# CLP_RV_A_1.net
KiCad netlist of a schematic drawn in Altium Designer
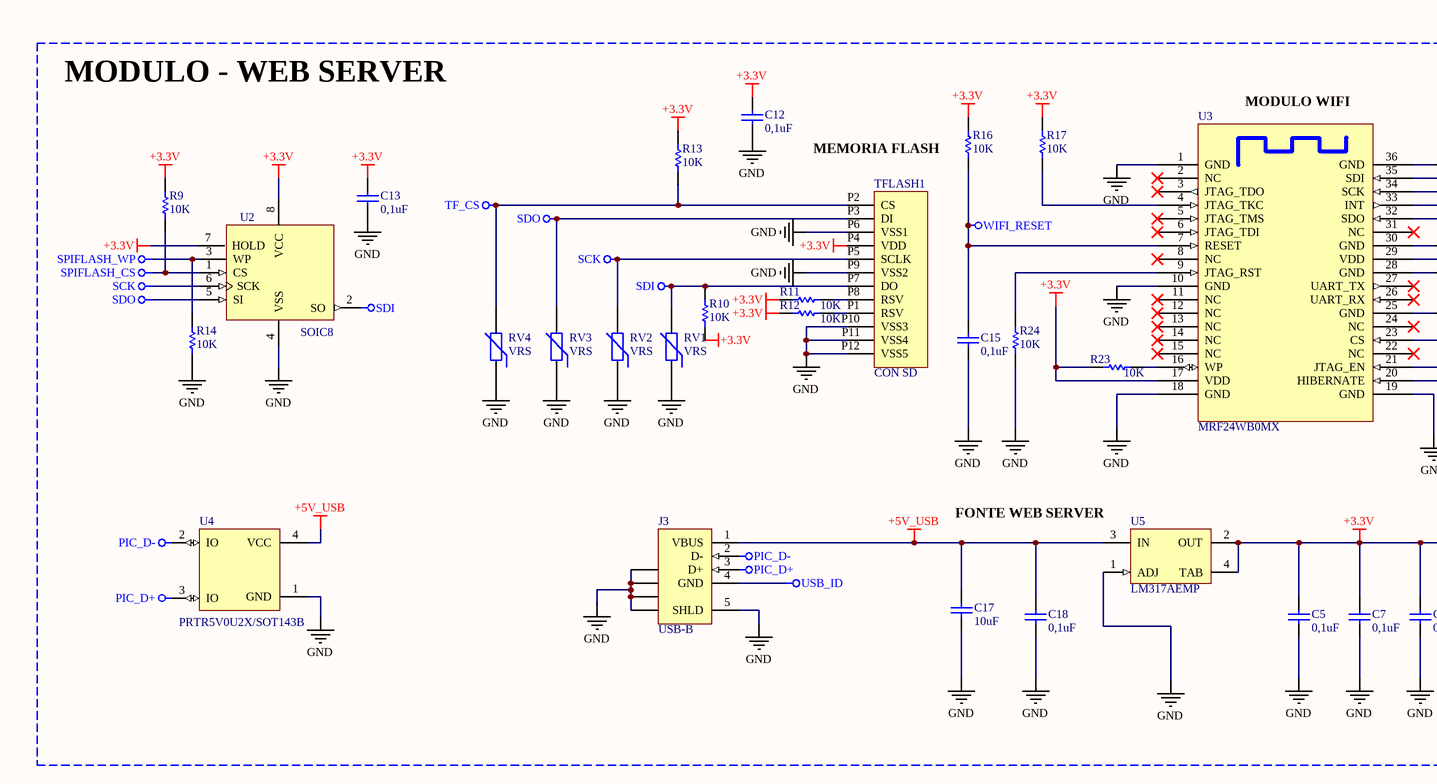
[diagram p0: CLP_RV_A.1.SchDoc, top left]
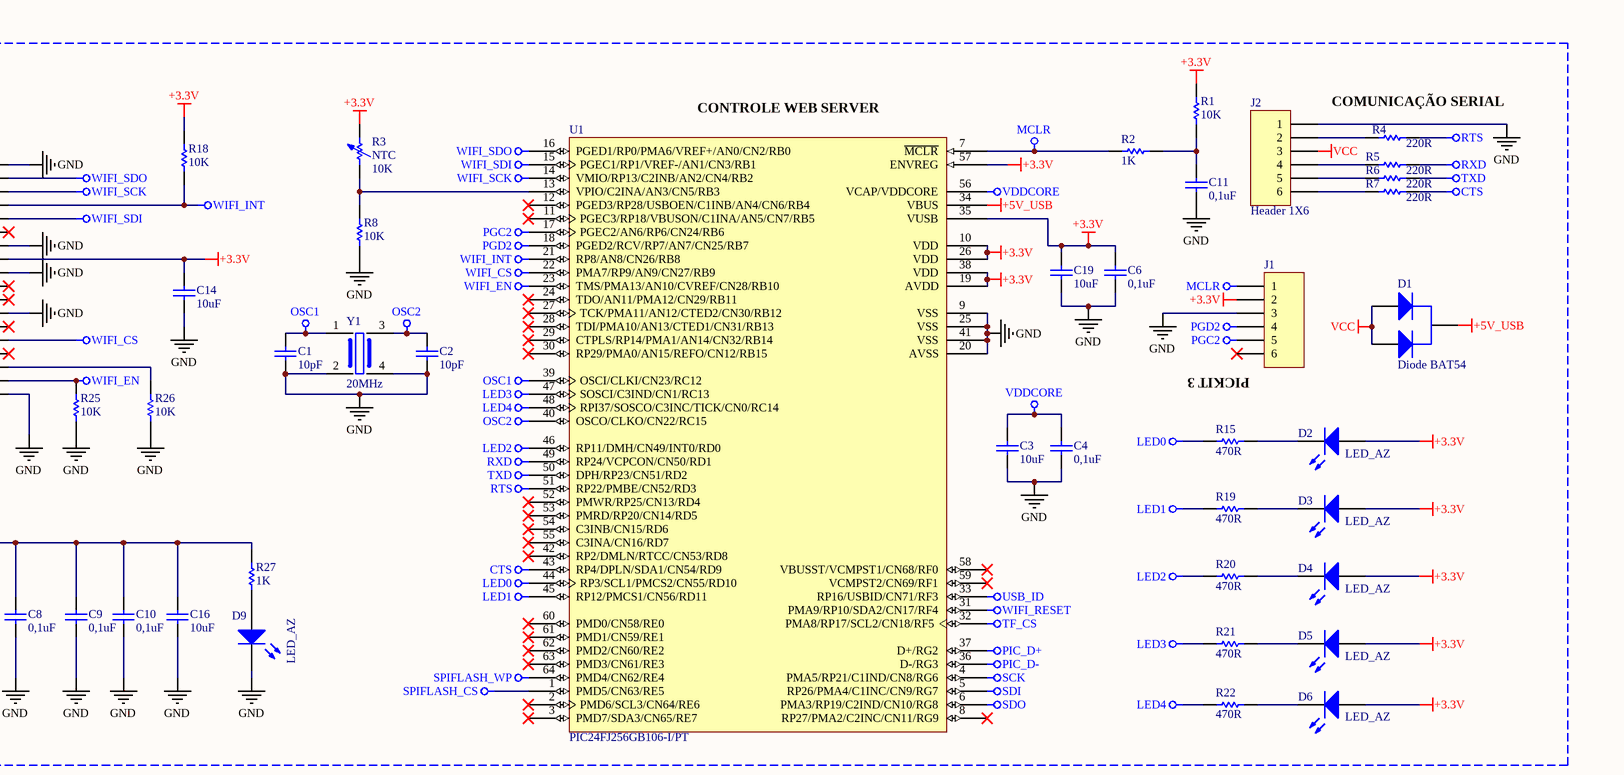
[diagram p1: CLP_RV_A.1.SchDoc, top right]
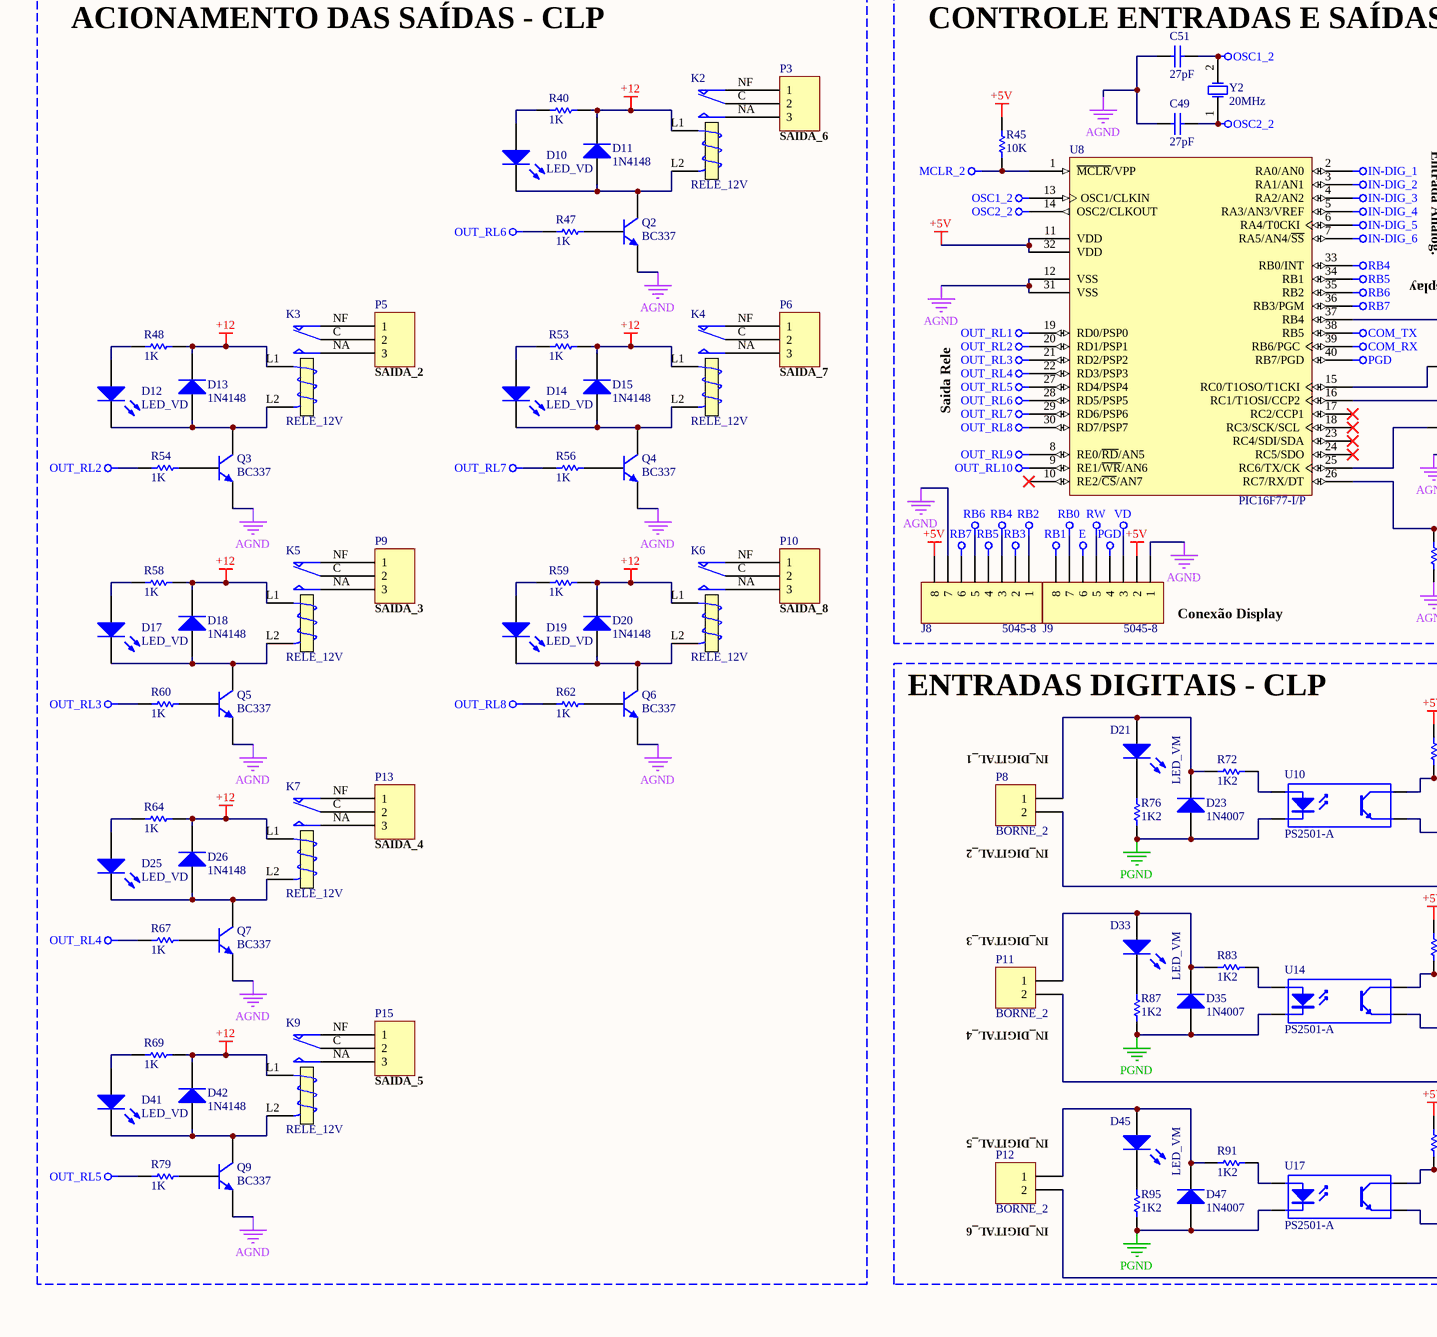
[diagram p2: CLP_RV_A.1.SchDoc, bottom left]
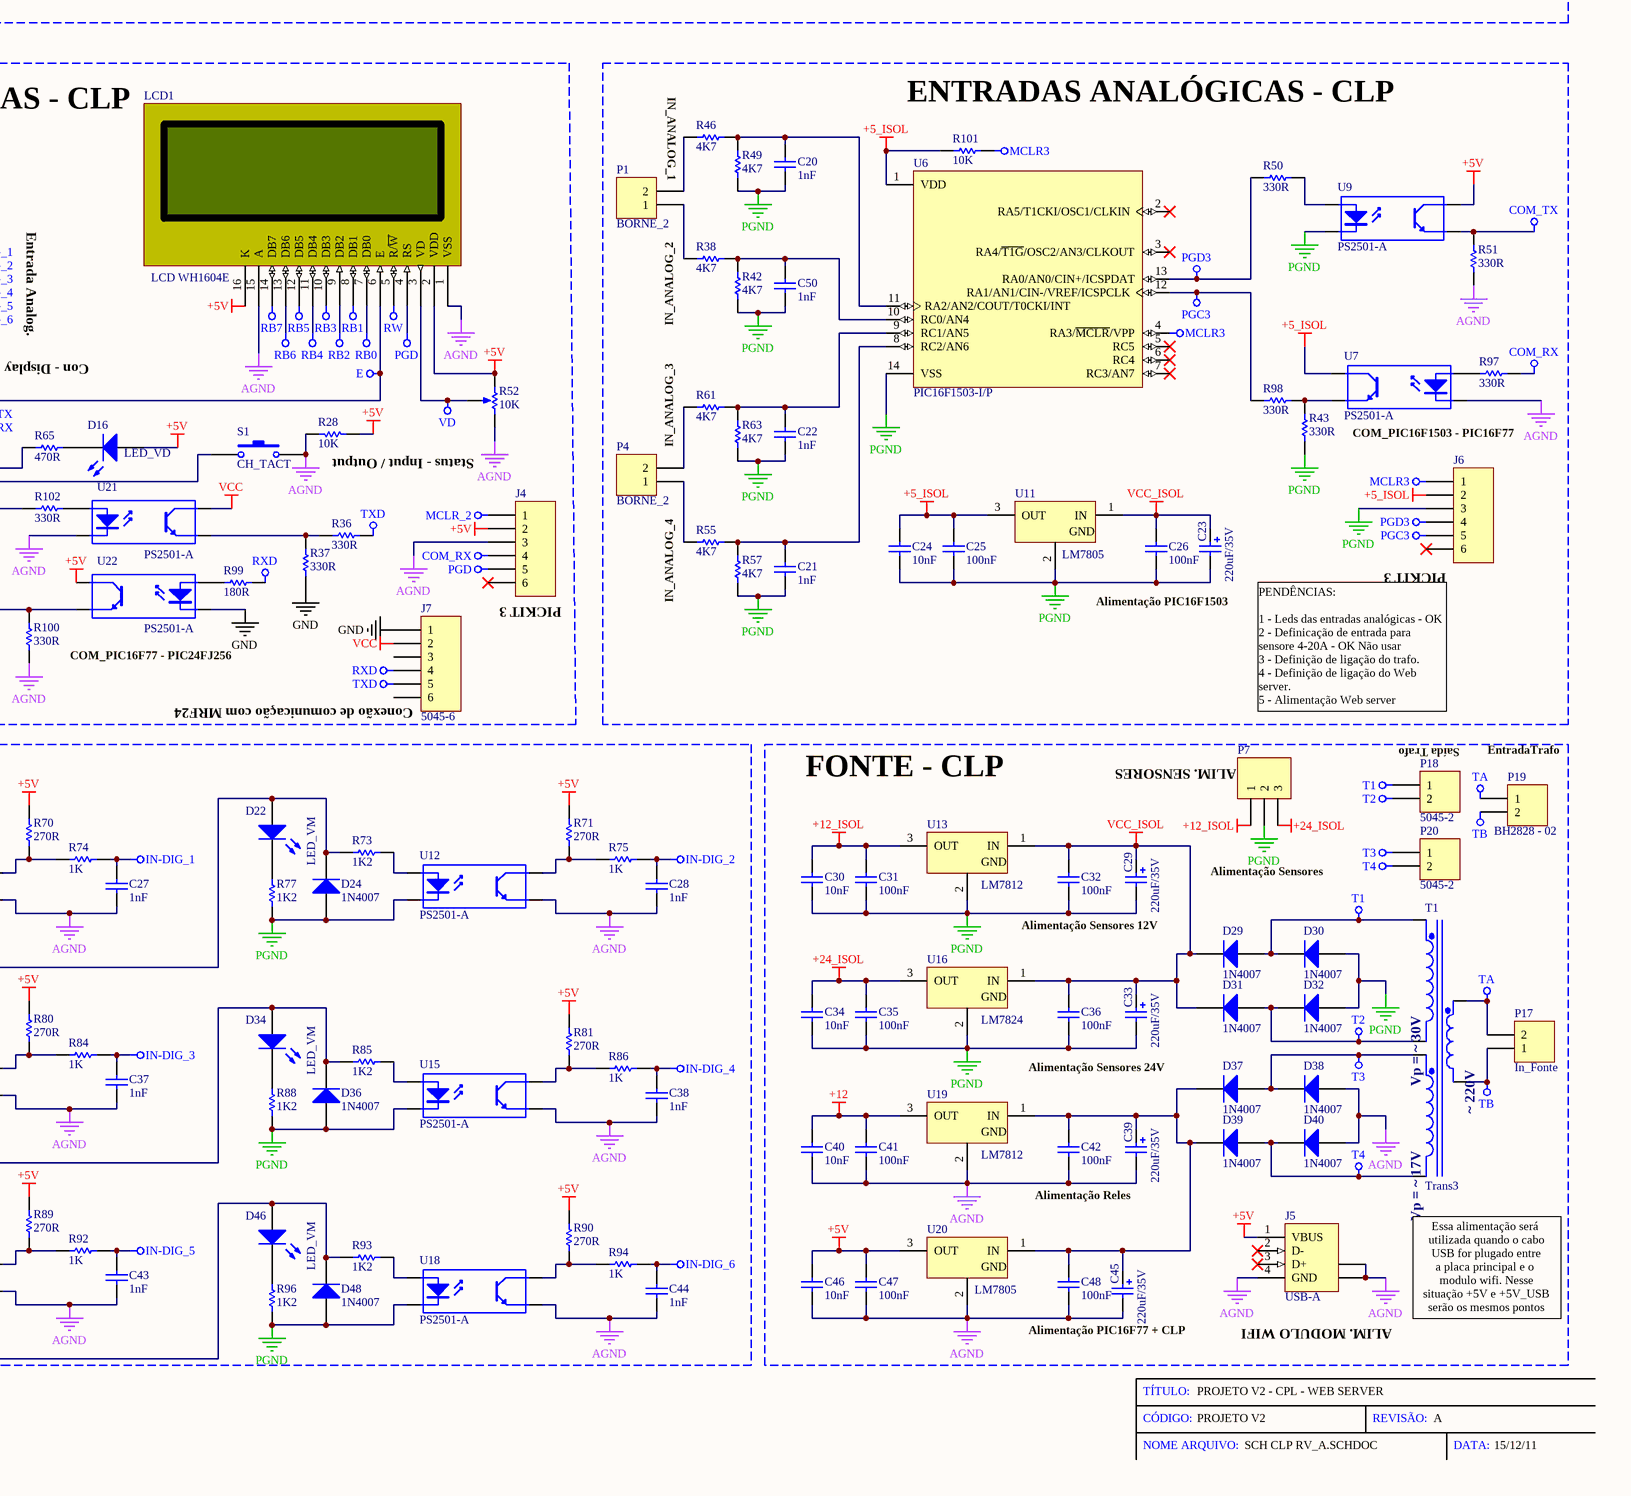
[diagram p3: CLP_RV_A.1.SchDoc, bottom right]

(export (version "E")
  (design (tool "Eeschema 10.0.6"))
  (components
    (comp (ref "C1")
      (value "10pF")
      (footprint "AR_0603_C")
      (description "CAP 0603 10pF - SMD")
      (fields (field (name "PUBLISHER") "Altium Limited"))
      (libsource (lib "LIB") (part "CAP 0603 10pF - SMD"))
    )
    (comp (ref "C2")
      (value "10pF")
      (footprint "AR_0603_C")
      (description "CAP 0603 10pF - SMD")
      (fields (field (name "PUBLISHER") "Altium Limited"))
      (libsource (lib "LIB") (part "CAP 0603 10pF - SMD"))
    )
    (comp (ref "C3")
      (value "10uF")
      (footprint "AR_0805_C")
      (description "CAP 0805 10uF - SMD")
      (fields (field (name "PUBLISHER") "Altium Limited"))
      (libsource (lib "LIB") (part "CAP 0805 10uF - SMD"))
    )
    (comp (ref "C4")
      (value "0,1uF")
      (footprint "AR_0603_C")
      (description "CAP 0603 0,1uF - SMD")
      (fields (field (name "PUBLISHER") "Altium Limited"))
      (libsource (lib "LIB") (part "CAP 0603 0,1uF - SMD"))
    )
    (comp (ref "C5")
      (value "0,1uF")
      (footprint "AR_0603_C")
      (description "CAP 0603 0,1uF - SMD")
      (fields (field (name "PUBLISHER") "Altium Limited"))
      (libsource (lib "LIB") (part "CAP 0603 0,1uF - SMD"))
    )
    (comp (ref "C6")
      (value "0,1uF")
      (footprint "AR_0603_C")
      (description "CAP 0603 0,1uF - SMD")
      (fields (field (name "PUBLISHER") "Altium Limited"))
      (libsource (lib "LIB") (part "CAP 0603 0,1uF - SMD"))
    )
    (comp (ref "C7")
      (value "0,1uF")
      (footprint "AR_0603_C")
      (description "CAP 0603 0,1uF - SMD")
      (fields (field (name "PUBLISHER") "Altium Limited"))
      (libsource (lib "LIB") (part "CAP 0603 0,1uF - SMD"))
    )
    (comp (ref "C8")
      (value "0,1uF")
      (footprint "AR_0603_C")
      (description "CAP 0603 0,1uF - SMD")
      (fields (field (name "PUBLISHER") "Altium Limited"))
      (libsource (lib "LIB") (part "CAP 0603 0,1uF - SMD"))
    )
    (comp (ref "C9")
      (value "0,1uF")
      (footprint "AR_0603_C")
      (description "CAP 0603 0,1uF - SMD")
      (fields (field (name "PUBLISHER") "Altium Limited"))
      (libsource (lib "LIB") (part "CAP 0603 0,1uF - SMD"))
    )
    (comp (ref "C10")
      (value "0,1uF")
      (footprint "AR_0603_C")
      (description "CAP 0603 0,1uF - SMD")
      (fields (field (name "PUBLISHER") "Altium Limited"))
      (libsource (lib "LIB") (part "CAP 0603 0,1uF - SMD"))
    )
    (comp (ref "C11")
      (value "0,1uF")
      (footprint "AR_0603_C")
      (description "CAP 0603 0,1uF - SMD")
      (fields (field (name "PUBLISHER") "Altium Limited"))
      (libsource (lib "LIB") (part "CAP 0603 0,1uF - SMD"))
    )
    (comp (ref "C12")
      (value "0,1uF")
      (footprint "AR_0603_C")
      (description "CAP 0603 0,1uF - SMD")
      (fields (field (name "PUBLISHER") "Altium Limited"))
      (libsource (lib "LIB") (part "CAP 0603 0,1uF - SMD"))
    )
    (comp (ref "C13")
      (value "0,1uF")
      (footprint "AR_0603_C")
      (description "CAP 0603 0,1uF - SMD")
      (fields (field (name "PUBLISHER") "Altium Limited"))
      (libsource (lib "LIB") (part "CAP 0603 0,1uF - SMD"))
    )
    (comp (ref "C14")
      (value "10uF")
      (footprint "AR_0805_C")
      (description "CAP 0805 10uF - SMD")
      (fields (field (name "PUBLISHER") "Altium Limited"))
      (libsource (lib "LIB") (part "CAP 0805 10uF - SMD"))
    )
    (comp (ref "C15")
      (value "0,1uF")
      (footprint "AR_0603_C")
      (description "CAP 0603 0,1uF - SMD")
      (fields (field (name "PUBLISHER") "Altium Limited"))
      (libsource (lib "LIB") (part "CAP 0603 0,1uF - SMD"))
    )
    (comp (ref "C16")
      (value "10uF")
      (footprint "AR_0805_C")
      (description "CAP 0805 10uF - SMD")
      (fields (field (name "PUBLISHER") "Altium Limited"))
      (libsource (lib "LIB") (part "CAP 0805 10uF - SMD"))
    )
    (comp (ref "C17")
      (value "10uF")
      (footprint "AR_0805_C")
      (description "CAP 0805 10uF - SMD")
      (fields (field (name "PUBLISHER") "Altium Limited"))
      (libsource (lib "LIB") (part "CAP 0805 10uF - SMD"))
    )
    (comp (ref "C18")
      (value "0,1uF")
      (footprint "AR_0603_C")
      (description "CAP 0603 0,1uF - SMD")
      (fields (field (name "PUBLISHER") "Altium Limited"))
      (libsource (lib "LIB") (part "CAP 0603 0,1uF - SMD"))
    )
    (comp (ref "C19")
      (value "10uF")
      (footprint "AR_0805_C")
      (description "CAP 0805 10uF - SMD")
      (fields (field (name "PUBLISHER") "Altium Limited"))
      (libsource (lib "LIB") (part "CAP 0805 10uF - SMD"))
    )
    (comp (ref "C20")
      (value "1nF")
      (footprint "CAP_AX_5_CER")
      (description "CAP CER 1nF / 25V")
      (fields (field (name "PUBLISHER") "Altium Limited"))
      (libsource (lib "LIB") (part "CAP CER 1nF / 25V"))
    )
    (comp (ref "C21")
      (value "1nF")
      (footprint "CAP_AX_5_CER")
      (description "CAP CER 1nF / 25V")
      (fields (field (name "PUBLISHER") "Altium Limited"))
      (libsource (lib "LIB") (part "CAP CER 1nF / 25V"))
    )
    (comp (ref "C22")
      (value "1nF")
      (footprint "CAP_AX_5_CER")
      (description "CAP CER 1nF / 25V")
      (fields (field (name "PUBLISHER") "Altium Limited"))
      (libsource (lib "LIB") (part "CAP CER 1nF / 25V"))
    )
    (comp (ref "C23")
      (value "220uF/35V")
      (footprint "CAP_RD_5_10")
      (description "CAP ELCO 220uF / 35V")
      (fields (field (name "PUBLISHER") "Altium Limited"))
      (libsource (lib "LIB") (part "CAP ELCO 220uF / 35V"))
    )
    (comp (ref "C24")
      (value "10nF")
      (footprint "CAP_AX_5_CER")
      (description "CAP CER 10nF / 25V")
      (fields (field (name "PUBLISHER") "Altium Limited"))
      (libsource (lib "LIB") (part "CAP CER 10nF / 25V"))
    )
    (comp (ref "C25")
      (value "100nF")
      (footprint "CAP_AX_5")
      (description "CAP CER 100nF / 63V")
      (fields (field (name "PUBLISHER") "Altium Limited"))
      (libsource (lib "LIB") (part "CAP CER 100nF / 63V"))
    )
    (comp (ref "C26")
      (value "100nF")
      (footprint "CAP_AX_5")
      (description "CAP CER 100nF / 63V")
      (fields (field (name "PUBLISHER") "Altium Limited"))
      (libsource (lib "LIB") (part "CAP CER 100nF / 63V"))
    )
    (comp (ref "C27")
      (value "1nF")
      (footprint "CAP_AX_5_CER")
      (description "CAP CER 1nF / 25V")
      (fields (field (name "PUBLISHER") "Altium Limited"))
      (libsource (lib "LIB") (part "CAP CER 1nF / 25V"))
    )
    (comp (ref "C28")
      (value "1nF")
      (footprint "CAP_AX_5_CER")
      (description "CAP CER 1nF / 25V")
      (fields (field (name "PUBLISHER") "Altium Limited"))
      (libsource (lib "LIB") (part "CAP CER 1nF / 25V"))
    )
    (comp (ref "C29")
      (value "220uF/35V")
      (footprint "CAP_RD_5_10")
      (description "CAP ELCO 220uF / 35V")
      (fields (field (name "PUBLISHER") "Altium Limited"))
      (libsource (lib "LIB") (part "CAP ELCO 220uF / 35V"))
    )
    (comp (ref "C30")
      (value "10nF")
      (footprint "CAP_AX_5_CER")
      (description "CAP CER 10nF / 25V")
      (fields (field (name "PUBLISHER") "Altium Limited"))
      (libsource (lib "LIB") (part "CAP CER 10nF / 25V"))
    )
    (comp (ref "C31")
      (value "100nF")
      (footprint "CAP_AX_5")
      (description "CAP CER 100nF / 63V")
      (fields (field (name "PUBLISHER") "Altium Limited"))
      (libsource (lib "LIB") (part "CAP CER 100nF / 63V"))
    )
    (comp (ref "C32")
      (value "100nF")
      (footprint "CAP_AX_5")
      (description "CAP CER 100nF / 63V")
      (fields (field (name "PUBLISHER") "Altium Limited"))
      (libsource (lib "LIB") (part "CAP CER 100nF / 63V"))
    )
    (comp (ref "C33")
      (value "220uF/35V")
      (footprint "CAP_RD_5_10")
      (description "CAP ELCO 220uF / 35V")
      (fields (field (name "PUBLISHER") "Altium Limited"))
      (libsource (lib "LIB") (part "CAP ELCO 220uF / 35V"))
    )
    (comp (ref "C34")
      (value "10nF")
      (footprint "CAP_AX_5_CER")
      (description "CAP CER 10nF / 25V")
      (fields (field (name "PUBLISHER") "Altium Limited"))
      (libsource (lib "LIB") (part "CAP CER 10nF / 25V"))
    )
    (comp (ref "C35")
      (value "100nF")
      (footprint "CAP_AX_5")
      (description "CAP CER 100nF / 63V")
      (fields (field (name "PUBLISHER") "Altium Limited"))
      (libsource (lib "LIB") (part "CAP CER 100nF / 63V"))
    )
    (comp (ref "C36")
      (value "100nF")
      (footprint "CAP_AX_5")
      (description "CAP CER 100nF / 63V")
      (fields (field (name "PUBLISHER") "Altium Limited"))
      (libsource (lib "LIB") (part "CAP CER 100nF / 63V"))
    )
    (comp (ref "C37")
      (value "1nF")
      (footprint "CAP_AX_5_CER")
      (description "CAP CER 1nF / 25V")
      (fields (field (name "PUBLISHER") "Altium Limited"))
      (libsource (lib "LIB") (part "CAP CER 1nF / 25V"))
    )
    (comp (ref "C38")
      (value "1nF")
      (footprint "CAP_AX_5_CER")
      (description "CAP CER 1nF / 25V")
      (fields (field (name "PUBLISHER") "Altium Limited"))
      (libsource (lib "LIB") (part "CAP CER 1nF / 25V"))
    )
    (comp (ref "C39")
      (value "220uF/35V")
      (footprint "CAP_RD_5_10")
      (description "CAP ELCO 220uF / 35V")
      (fields (field (name "PUBLISHER") "Altium Limited"))
      (libsource (lib "LIB") (part "CAP ELCO 220uF / 35V"))
    )
    (comp (ref "C40")
      (value "10nF")
      (footprint "CAP_AX_5_CER")
      (description "CAP CER 10nF / 25V")
      (fields (field (name "PUBLISHER") "Altium Limited"))
      (libsource (lib "LIB") (part "CAP CER 10nF / 25V"))
    )
    (comp (ref "C41")
      (value "100nF")
      (footprint "CAP_AX_5")
      (description "CAP CER 100nF / 63V")
      (fields (field (name "PUBLISHER") "Altium Limited"))
      (libsource (lib "LIB") (part "CAP CER 100nF / 63V"))
    )
    (comp (ref "C42")
      (value "100nF")
      (footprint "CAP_AX_5")
      (description "CAP CER 100nF / 63V")
      (fields (field (name "PUBLISHER") "Altium Limited"))
      (libsource (lib "LIB") (part "CAP CER 100nF / 63V"))
    )
    (comp (ref "C43")
      (value "1nF")
      (footprint "CAP_AX_5_CER")
      (description "CAP CER 1nF / 25V")
      (fields (field (name "PUBLISHER") "Altium Limited"))
      (libsource (lib "LIB") (part "CAP CER 1nF / 25V"))
    )
    (comp (ref "C44")
      (value "1nF")
      (footprint "CAP_AX_5_CER")
      (description "CAP CER 1nF / 25V")
      (fields (field (name "PUBLISHER") "Altium Limited"))
      (libsource (lib "LIB") (part "CAP CER 1nF / 25V"))
    )
    (comp (ref "C45")
      (value "220uF/35V")
      (footprint "CAP_RD_5_10")
      (description "CAP ELCO 220uF / 35V")
      (fields (field (name "PUBLISHER") "Altium Limited"))
      (libsource (lib "LIB") (part "CAP ELCO 220uF / 35V"))
    )
    (comp (ref "C46")
      (value "10nF")
      (footprint "CAP_AX_5_CER")
      (description "CAP CER 10nF / 25V")
      (fields (field (name "PUBLISHER") "Altium Limited"))
      (libsource (lib "LIB") (part "CAP CER 10nF / 25V"))
    )
    (comp (ref "C47")
      (value "100nF")
      (footprint "CAP_AX_5")
      (description "CAP CER 100nF / 63V")
      (fields (field (name "PUBLISHER") "Altium Limited"))
      (libsource (lib "LIB") (part "CAP CER 100nF / 63V"))
    )
    (comp (ref "C48")
      (value "100nF")
      (footprint "CAP_AX_5")
      (description "CAP CER 100nF / 63V")
      (fields (field (name "PUBLISHER") "Altium Limited"))
      (libsource (lib "LIB") (part "CAP CER 100nF / 63V"))
    )
    (comp (ref "C49")
      (value "27pF")
      (footprint "CAP_AX_5_CER")
      (description "CAP CER 27pF / 25V")
      (fields (field (name "PUBLISHER") "Altium Limited"))
      (libsource (lib "LIB") (part "CAP CER 27pF / 25V"))
    )
    (comp (ref "C50")
      (value "1nF")
      (footprint "CAP_AX_5_CER")
      (description "CAP CER 1nF / 25V")
      (fields (field (name "PUBLISHER") "Altium Limited"))
      (libsource (lib "LIB") (part "CAP CER 1nF / 25V"))
    )
    (comp (ref "C51")
      (value "27pF")
      (footprint "CAP_AX_5_CER")
      (description "CAP CER 27pF / 25V")
      (fields (field (name "PUBLISHER") "Altium Limited"))
      (libsource (lib "LIB") (part "CAP CER 27pF / 25V"))
    )
    (comp (ref "D1")
      (value "Diode BAT54")
      (footprint "AR_SOT23")
      (description "Low-Loss RF Switching Diode")
      (libsource (lib "LIB") (part "Diode BAT54"))
    )
    (comp (ref "D2")
      (value "LED_AZ")
      (footprint "AR_0603_L_AZ")
      (description "LED 0603 AZUL - SMD")
      (fields (field (name "PUBLISHER") "Altium Limited"))
      (libsource (lib "LIB") (part "LED 0603 AZUL - SMD"))
    )
    (comp (ref "D3")
      (value "LED_AZ")
      (footprint "AR_0603_L_AZ")
      (description "LED 0603 AZUL - SMD")
      (fields (field (name "PUBLISHER") "Altium Limited"))
      (libsource (lib "LIB") (part "LED 0603 AZUL - SMD"))
    )
    (comp (ref "D4")
      (value "LED_AZ")
      (footprint "AR_0603_L_AZ")
      (description "LED 0603 AZUL - SMD")
      (fields (field (name "PUBLISHER") "Altium Limited"))
      (libsource (lib "LIB") (part "LED 0603 AZUL - SMD"))
    )
    (comp (ref "D5")
      (value "LED_AZ")
      (footprint "AR_0603_L_AZ")
      (description "LED 0603 AZUL - SMD")
      (fields (field (name "PUBLISHER") "Altium Limited"))
      (libsource (lib "LIB") (part "LED 0603 AZUL - SMD"))
    )
    (comp (ref "D6")
      (value "LED_AZ")
      (footprint "AR_0603_L_AZ")
      (description "LED 0603 AZUL - SMD")
      (fields (field (name "PUBLISHER") "Altium Limited"))
      (libsource (lib "LIB") (part "LED 0603 AZUL - SMD"))
    )
    (comp (ref "D9")
      (value "LED_AZ")
      (footprint "AR_0603_L_AZ")
      (description "LED 0603 AZUL - SMD")
      (fields (field (name "PUBLISHER") "Altium Limited"))
      (libsource (lib "LIB") (part "LED 0603 AZUL - SMD"))
    )
    (comp (ref "D10")
      (value "LED_VD")
      (footprint "LED_VD")
      (description "LED_VD_3MM")
      (fields (field (name "PUBLISHER") "Altium Limited"))
      (libsource (lib "LIB") (part "LED_VD_3MM"))
    )
    (comp (ref "D11")
      (value "1N4148")
      (footprint "1N414X")
      (description "DIODO 1N4148")
      (fields (field (name "PUBLISHER") "Altium Limited"))
      (libsource (lib "LIB") (part "DIODO 1N4148"))
    )
    (comp (ref "D12")
      (value "LED_VD")
      (footprint "LED_VD")
      (description "LED_VD_3MM")
      (fields (field (name "PUBLISHER") "Altium Limited"))
      (libsource (lib "LIB") (part "LED_VD_3MM"))
    )
    (comp (ref "D13")
      (value "1N4148")
      (footprint "1N414X")
      (description "DIODO 1N4148")
      (fields (field (name "PUBLISHER") "Altium Limited"))
      (libsource (lib "LIB") (part "DIODO 1N4148"))
    )
    (comp (ref "D14")
      (value "LED_VD")
      (footprint "LED_VD")
      (description "LED_VD_3MM")
      (fields (field (name "PUBLISHER") "Altium Limited"))
      (libsource (lib "LIB") (part "LED_VD_3MM"))
    )
    (comp (ref "D15")
      (value "1N4148")
      (footprint "1N414X")
      (description "DIODO 1N4148")
      (fields (field (name "PUBLISHER") "Altium Limited"))
      (libsource (lib "LIB") (part "DIODO 1N4148"))
    )
    (comp (ref "D16")
      (value "LED_VD")
      (footprint "LED_VD")
      (description "LED_VD_3MM")
      (fields (field (name "PUBLISHER") "Altium Limited"))
      (libsource (lib "LIB") (part "LED_VD_3MM"))
    )
    (comp (ref "D17")
      (value "LED_VD")
      (footprint "LED_VD")
      (description "LED_VD_3MM")
      (fields (field (name "PUBLISHER") "Altium Limited"))
      (libsource (lib "LIB") (part "LED_VD_3MM"))
    )
    (comp (ref "D18")
      (value "1N4148")
      (footprint "1N414X")
      (description "DIODO 1N4148")
      (fields (field (name "PUBLISHER") "Altium Limited"))
      (libsource (lib "LIB") (part "DIODO 1N4148"))
    )
    (comp (ref "D19")
      (value "LED_VD")
      (footprint "LED_VD")
      (description "LED_VD_3MM")
      (fields (field (name "PUBLISHER") "Altium Limited"))
      (libsource (lib "LIB") (part "LED_VD_3MM"))
    )
    (comp (ref "D20")
      (value "1N4148")
      (footprint "1N414X")
      (description "DIODO 1N4148")
      (fields (field (name "PUBLISHER") "Altium Limited"))
      (libsource (lib "LIB") (part "DIODO 1N4148"))
    )
    (comp (ref "D21")
      (value "LED_VM")
      (footprint "LED_VM")
      (description "LED_VM_3MM")
      (fields (field (name "PUBLISHER") "Altium Limited"))
      (libsource (lib "LIB") (part "LED_VM_3MM"))
    )
    (comp (ref "D22")
      (value "LED_VM")
      (footprint "LED_VM")
      (description "LED_VM_3MM")
      (fields (field (name "PUBLISHER") "Altium Limited"))
      (libsource (lib "LIB") (part "LED_VM_3MM"))
    )
    (comp (ref "D23")
      (value "1N4007")
      (footprint "1N400X")
      (description "DIODO 1N4007")
      (fields (field (name "PUBLISHER") "Altium Limited"))
      (libsource (lib "LIB") (part "DIODO 1N4007"))
    )
    (comp (ref "D24")
      (value "1N4007")
      (footprint "1N400X")
      (description "DIODO 1N4007")
      (fields (field (name "PUBLISHER") "Altium Limited"))
      (libsource (lib "LIB") (part "DIODO 1N4007"))
    )
    (comp (ref "D25")
      (value "LED_VD")
      (footprint "LED_VD")
      (description "LED_VD_3MM")
      (fields (field (name "PUBLISHER") "Altium Limited"))
      (libsource (lib "LIB") (part "LED_VD_3MM"))
    )
    (comp (ref "D26")
      (value "1N4148")
      (footprint "1N414X")
      (description "DIODO 1N4148")
      (fields (field (name "PUBLISHER") "Altium Limited"))
      (libsource (lib "LIB") (part "DIODO 1N4148"))
    )
    (comp (ref "D29")
      (value "1N4007")
      (footprint "1N400X")
      (description "DIODO 1N4007")
      (fields (field (name "PUBLISHER") "Altium Limited"))
      (libsource (lib "LIB") (part "DIODO 1N4007"))
    )
    (comp (ref "D30")
      (value "1N4007")
      (footprint "1N400X")
      (description "DIODO 1N4007")
      (fields (field (name "PUBLISHER") "Altium Limited"))
      (libsource (lib "LIB") (part "DIODO 1N4007"))
    )
    (comp (ref "D31")
      (value "1N4007")
      (footprint "1N400X")
      (description "DIODO 1N4007")
      (fields (field (name "PUBLISHER") "Altium Limited"))
      (libsource (lib "LIB") (part "DIODO 1N4007"))
    )
    (comp (ref "D32")
      (value "1N4007")
      (footprint "1N400X")
      (description "DIODO 1N4007")
      (fields (field (name "PUBLISHER") "Altium Limited"))
      (libsource (lib "LIB") (part "DIODO 1N4007"))
    )
    (comp (ref "D33")
      (value "LED_VM")
      (footprint "LED_VM")
      (description "LED_VM_3MM")
      (fields (field (name "PUBLISHER") "Altium Limited"))
      (libsource (lib "LIB") (part "LED_VM_3MM"))
    )
    (comp (ref "D34")
      (value "LED_VM")
      (footprint "LED_VM")
      (description "LED_VM_3MM")
      (fields (field (name "PUBLISHER") "Altium Limited"))
      (libsource (lib "LIB") (part "LED_VM_3MM"))
    )
    (comp (ref "D35")
      (value "1N4007")
      (footprint "1N400X")
      (description "DIODO 1N4007")
      (fields (field (name "PUBLISHER") "Altium Limited"))
      (libsource (lib "LIB") (part "DIODO 1N4007"))
    )
    (comp (ref "D36")
      (value "1N4007")
      (footprint "1N400X")
      (description "DIODO 1N4007")
      (fields (field (name "PUBLISHER") "Altium Limited"))
      (libsource (lib "LIB") (part "DIODO 1N4007"))
    )
    (comp (ref "D37")
      (value "1N4007")
      (footprint "1N400X")
      (description "DIODO 1N4007")
      (fields (field (name "PUBLISHER") "Altium Limited"))
      (libsource (lib "LIB") (part "DIODO 1N4007"))
    )
    (comp (ref "D38")
      (value "1N4007")
      (footprint "1N400X")
      (description "DIODO 1N4007")
      (fields (field (name "PUBLISHER") "Altium Limited"))
      (libsource (lib "LIB") (part "DIODO 1N4007"))
    )
    (comp (ref "D39")
      (value "1N4007")
      (footprint "1N400X")
      (description "DIODO 1N4007")
      (fields (field (name "PUBLISHER") "Altium Limited"))
      (libsource (lib "LIB") (part "DIODO 1N4007"))
    )
    (comp (ref "D40")
      (value "1N4007")
      (footprint "1N400X")
      (description "DIODO 1N4007")
      (fields (field (name "PUBLISHER") "Altium Limited"))
      (libsource (lib "LIB") (part "DIODO 1N4007"))
    )
    (comp (ref "D41")
      (value "LED_VD")
      (footprint "LED_VD")
      (description "LED_VD_3MM")
      (fields (field (name "PUBLISHER") "Altium Limited"))
      (libsource (lib "LIB") (part "LED_VD_3MM"))
    )
    (comp (ref "D42")
      (value "1N4148")
      (footprint "1N414X")
      (description "DIODO 1N4148")
      (fields (field (name "PUBLISHER") "Altium Limited"))
      (libsource (lib "LIB") (part "DIODO 1N4148"))
    )
    (comp (ref "D45")
      (value "LED_VM")
      (footprint "LED_VM")
      (description "LED_VM_3MM")
      (fields (field (name "PUBLISHER") "Altium Limited"))
      (libsource (lib "LIB") (part "LED_VM_3MM"))
    )
    (comp (ref "D46")
      (value "LED_VM")
      (footprint "LED_VM")
      (description "LED_VM_3MM")
      (fields (field (name "PUBLISHER") "Altium Limited"))
      (libsource (lib "LIB") (part "LED_VM_3MM"))
    )
    (comp (ref "D47")
      (value "1N4007")
      (footprint "1N400X")
      (description "DIODO 1N4007")
      (fields (field (name "PUBLISHER") "Altium Limited"))
      (libsource (lib "LIB") (part "DIODO 1N4007"))
    )
    (comp (ref "D48")
      (value "1N4007")
      (footprint "1N400X")
      (description "DIODO 1N4007")
      (fields (field (name "PUBLISHER") "Altium Limited"))
      (libsource (lib "LIB") (part "DIODO 1N4007"))
    )
    (comp (ref "J1")
      (value "Header 1X6")
      (footprint "BARRA DE PINO RETA 1 X 7")
      (description "Barra de Pino 1X6")
      (fields (field (name "PUBLISHER") "Altium Limited"))
      (libsource (lib "") (part "Barra de Pino 1X6_1"))
    )
    (comp (ref "J2")
      (value "Header 1X6")
      (footprint "BARRA DE PINO RETA 1 X 7")
      (description "Barra de Pino 1X6")
      (fields (field (name "PUBLISHER") "Altium Limited"))
      (libsource (lib "LIB") (part "Barra de Pino 1X6"))
    )
    (comp (ref "J3")
      (value "USB-B")
      (footprint "CON_USB_SMD_B")
      (description "USB 2.0, Right Angle, SMT, B Type, Receptacle, 5 Position, Black")
      (fields (field (name "PUBLISHER") "Altium Limited"))
      (libsource (lib "LIB") (part "CON_USB_SMD_B"))
    )
    (comp (ref "J4")
      (value "PICKIT 3")
      (footprint "BARRA DE PINO RETA 1 X 7")
      (description "Barra de Pino 1X6")
      (fields (field (name "PUBLISHER") "Altium Limited"))
      (libsource (lib "") (part "Barra de Pino 1X6_1"))
    )
    (comp (ref "J5")
      (value "USB-A")
      (footprint "CON_USB_PTH_A")
      (description "USB 1.1, Right Angle, Thru-Hole, Reverse Type, Receptacle, 4 Position, Black")
      (fields (field (name "PUBLISHER") "Altium Limited"))
      (libsource (lib "LIB") (part "CON_USB_PTH_A"))
    )
    (comp (ref "J6")
      (value "PICKIT 3")
      (footprint "BARRA DE PINO RETA 1 X 7")
      (description "Barra de Pino 1X6")
      (fields (field (name "PUBLISHER") "Altium Limited"))
      (libsource (lib "") (part "Barra de Pino 1X6_1"))
    )
    (comp (ref "J7")
      (value "5045-6")
      (footprint "BC5045-06")
      (description "BASE CONEC. 5045-6")
      (fields (field (name "PUBLISHER") "Altium Limited"))
      (libsource (lib "LIB") (part "BASE CONEC. 5045-6"))
    )
    (comp (ref "J8")
      (value "5045-8")
      (footprint "BC5045-08")
      (description "BASE CONEC. 5045-8")
      (fields (field (name "PUBLISHER") "Altium Limited"))
      (libsource (lib "LIB") (part "BASE CONEC. 5045-8"))
    )
    (comp (ref "J9")
      (value "5045-8")
      (footprint "BC5045-08")
      (description "BASE CONEC. 5045-8")
      (fields (field (name "PUBLISHER") "Altium Limited"))
      (libsource (lib "LIB") (part "BASE CONEC. 5045-8"))
    )
    (comp (ref "K2")
      (value "RELE_12V")
      (footprint "RELE_M")
      (description "RELE 12V")
      (fields (field (name "PUBLISHER") "Altium Limited"))
      (libsource (lib "LIB") (part "RELE 12V"))
    )
    (comp (ref "K3")
      (value "RELE_12V")
      (footprint "RELE_M")
      (description "RELE 12V")
      (fields (field (name "PUBLISHER") "Altium Limited"))
      (libsource (lib "LIB") (part "RELE 12V"))
    )
    (comp (ref "K4")
      (value "RELE_12V")
      (footprint "RELE_M")
      (description "RELE 12V")
      (fields (field (name "PUBLISHER") "Altium Limited"))
      (libsource (lib "LIB") (part "RELE 12V"))
    )
    (comp (ref "K5")
      (value "RELE_12V")
      (footprint "RELE_M")
      (description "RELE 12V")
      (fields (field (name "PUBLISHER") "Altium Limited"))
      (libsource (lib "LIB") (part "RELE 12V"))
    )
    (comp (ref "K6")
      (value "RELE_12V")
      (footprint "RELE_M")
      (description "RELE 12V")
      (fields (field (name "PUBLISHER") "Altium Limited"))
      (libsource (lib "LIB") (part "RELE 12V"))
    )
    (comp (ref "K7")
      (value "RELE_12V")
      (footprint "RELE_M")
      (description "RELE 12V")
      (fields (field (name "PUBLISHER") "Altium Limited"))
      (libsource (lib "LIB") (part "RELE 12V"))
    )
    (comp (ref "K9")
      (value "RELE_12V")
      (footprint "RELE_M")
      (description "RELE 12V")
      (fields (field (name "PUBLISHER") "Altium Limited"))
      (libsource (lib "LIB") (part "RELE 12V"))
    )
    (comp (ref "LCD1")
      (value "LCD WH1604E")
      (footprint "WH1604")
      (description "Display Crístal Líquido WH1604E - 16X4")
      (libsource (lib "LIB") (part "LCD WH1604E"))
    )
    (comp (ref "P1")
      (value "BORNE_2")
      (footprint "BORNE_2")
      (description "BORNE_MOLEX_2")
      (fields (field (name "PUBLISHER") "Altium Limited"))
      (libsource (lib "") (part "BORNE_MOLEX_2_2"))
    )
    (comp (ref "P3")
      (value "SAIDA_6")
      (footprint "BORNE_3")
      (description "BORNE_MOLEX_3")
      (fields (field (name "PUBLISHER") "Altium Limited"))
      (libsource (lib "LIB") (part "BORNE_MOLEX_3"))
    )
    (comp (ref "P4")
      (value "BORNE_2")
      (footprint "BORNE_2")
      (description "BORNE_MOLEX_2")
      (fields (field (name "PUBLISHER") "Altium Limited"))
      (libsource (lib "") (part "BORNE_MOLEX_2_2"))
    )
    (comp (ref "P5")
      (value "SAIDA_2")
      (footprint "BORNE_3")
      (description "BORNE_MOLEX_3")
      (fields (field (name "PUBLISHER") "Altium Limited"))
      (libsource (lib "LIB") (part "BORNE_MOLEX_3"))
    )
    (comp (ref "P6")
      (value "SAIDA_7")
      (footprint "BORNE_3")
      (description "BORNE_MOLEX_3")
      (fields (field (name "PUBLISHER") "Altium Limited"))
      (libsource (lib "LIB") (part "BORNE_MOLEX_3"))
    )
    (comp (ref "P7")
      (value "Alimentação Sensores")
      (footprint "BORNE_3")
      (description "BORNE_MOLEX_3")
      (fields (field (name "PUBLISHER") "Altium Limited"))
      (libsource (lib "") (part "BORNE_MOLEX_3_1"))
    )
    (comp (ref "P8")
      (value "BORNE_2")
      (footprint "BORNE_2")
      (description "BORNE_MOLEX_2")
      (fields (field (name "PUBLISHER") "Altium Limited"))
      (libsource (lib "LIB") (part "BORNE_MOLEX_2"))
    )
    (comp (ref "P9")
      (value "SAIDA_3")
      (footprint "BORNE_3")
      (description "BORNE_MOLEX_3")
      (fields (field (name "PUBLISHER") "Altium Limited"))
      (libsource (lib "LIB") (part "BORNE_MOLEX_3"))
    )
    (comp (ref "P10")
      (value "SAIDA_8")
      (footprint "BORNE_3")
      (description "BORNE_MOLEX_3")
      (fields (field (name "PUBLISHER") "Altium Limited"))
      (libsource (lib "LIB") (part "BORNE_MOLEX_3"))
    )
    (comp (ref "P11")
      (value "BORNE_2")
      (footprint "BORNE_2")
      (description "BORNE_MOLEX_2")
      (fields (field (name "PUBLISHER") "Altium Limited"))
      (libsource (lib "LIB") (part "BORNE_MOLEX_2"))
    )
    (comp (ref "P12")
      (value "BORNE_2")
      (footprint "BORNE_2")
      (description "BORNE_MOLEX_2")
      (fields (field (name "PUBLISHER") "Altium Limited"))
      (libsource (lib "LIB") (part "BORNE_MOLEX_2"))
    )
    (comp (ref "P13")
      (value "SAIDA_4")
      (footprint "BORNE_3")
      (description "BORNE_MOLEX_3")
      (fields (field (name "PUBLISHER") "Altium Limited"))
      (libsource (lib "LIB") (part "BORNE_MOLEX_3"))
    )
    (comp (ref "P15")
      (value "SAIDA_5")
      (footprint "BORNE_3")
      (description "BORNE_MOLEX_3")
      (fields (field (name "PUBLISHER") "Altium Limited"))
      (libsource (lib "LIB") (part "BORNE_MOLEX_3"))
    )
    (comp (ref "P17")
      (value "In_Fonte")
      (footprint "BORNE_2")
      (description "BORNE_MOLEX_2")
      (fields (field (name "PUBLISHER") "Altium Limited"))
      (libsource (lib "") (part "BORNE_MOLEX_2_1"))
    )
    (comp (ref "P18")
      (value "5045-2")
      (footprint "BC5045-02")
      (description "BASE CONEC. 5045-2")
      (fields (field (name "PUBLISHER") "Altium Limited"))
      (libsource (lib "LIB") (part "BASE CONEC. 5045-2"))
    )
    (comp (ref "P19")
      (value "BH2828 - 02")
      (footprint "BOX_HEAD_2828-02")
      (description "Box Header BH2828 - 02")
      (fields (field (name "PUBLISHER") "Altium Limited"))
      (libsource (lib "LIB") (part "Box Header BH2828 - 02"))
    )
    (comp (ref "P20")
      (value "5045-2")
      (footprint "BC5045-02")
      (description "BASE CONEC. 5045-2")
      (fields (field (name "PUBLISHER") "Altium Limited"))
      (libsource (lib "LIB") (part "BASE CONEC. 5045-2"))
    )
    (comp (ref "Q2")
      (value "BC337")
      (footprint "TO-92")
      (description "TR BC337")
      (fields (field (name "PUBLISHER") "Altium Limited"))
      (libsource (lib "LIB") (part "TR BC337"))
    )
    (comp (ref "Q3")
      (value "BC337")
      (footprint "TO-92")
      (description "TR BC337")
      (fields (field (name "PUBLISHER") "Altium Limited"))
      (libsource (lib "LIB") (part "TR BC337"))
    )
    (comp (ref "Q4")
      (value "BC337")
      (footprint "TO-92")
      (description "TR BC337")
      (fields (field (name "PUBLISHER") "Altium Limited"))
      (libsource (lib "LIB") (part "TR BC337"))
    )
    (comp (ref "Q5")
      (value "BC337")
      (footprint "TO-92")
      (description "TR BC337")
      (fields (field (name "PUBLISHER") "Altium Limited"))
      (libsource (lib "LIB") (part "TR BC337"))
    )
    (comp (ref "Q6")
      (value "BC337")
      (footprint "TO-92")
      (description "TR BC337")
      (fields (field (name "PUBLISHER") "Altium Limited"))
      (libsource (lib "LIB") (part "TR BC337"))
    )
    (comp (ref "Q7")
      (value "BC337")
      (footprint "TO-92")
      (description "TR BC337")
      (fields (field (name "PUBLISHER") "Altium Limited"))
      (libsource (lib "LIB") (part "TR BC337"))
    )
    (comp (ref "Q9")
      (value "BC337")
      (footprint "TO-92")
      (description "TR BC337")
      (fields (field (name "PUBLISHER") "Altium Limited"))
      (libsource (lib "LIB") (part "TR BC337"))
    )
    (comp (ref "R1")
      (value "10K")
      (footprint "AR_0603_R")
      (description "RES 10K 0603 - SMD")
      (fields (field (name "PUBLISHER") "Altium Limited"))
      (libsource (lib "LIB") (part "RES 10K 0603 - SMD"))
    )
    (comp (ref "R2")
      (value "1K")
      (footprint "AR_0603_R")
      (description "RES 1K 0603 - SMD")
      (fields (field (name "PUBLISHER") "Altium Limited"))
      (libsource (lib "LIB") (part "RES 1K 0603 - SMD"))
    )
    (comp (ref "R3")
      (value "NTC")
      (footprint "AR_0603_I")
      (description "Variable Resistor")
      (fields (field (name "ALTIUM_VALUE") "10K") (field (name "PUBLISHER") "Altium Limited"))
      (libsource (lib "Miscellaneous Devices") (part "Res Adj1"))
    )
    (comp (ref "R4")
      (value "220R")
      (footprint "AR_0603_R")
      (description "RES 220R 0603 - SMD")
      (fields (field (name "PUBLISHER") "Altium Limited"))
      (libsource (lib "LIB") (part "RES 220R 0603 - SMD"))
    )
    (comp (ref "R5")
      (value "220R")
      (footprint "AR_0603_R")
      (description "RES 220R 0603 - SMD")
      (fields (field (name "PUBLISHER") "Altium Limited"))
      (libsource (lib "LIB") (part "RES 220R 0603 - SMD"))
    )
    (comp (ref "R6")
      (value "220R")
      (footprint "AR_0603_R")
      (description "RES 220R 0603 - SMD")
      (fields (field (name "PUBLISHER") "Altium Limited"))
      (libsource (lib "LIB") (part "RES 220R 0603 - SMD"))
    )
    (comp (ref "R7")
      (value "220R")
      (footprint "AR_0603_R")
      (description "RES 220R 0603 - SMD")
      (fields (field (name "PUBLISHER") "Altium Limited"))
      (libsource (lib "LIB") (part "RES 220R 0603 - SMD"))
    )
    (comp (ref "R8")
      (value "10K")
      (footprint "AR_0603_R")
      (description "RES 10K 0603 - SMD")
      (fields (field (name "PUBLISHER") "Altium Limited"))
      (libsource (lib "LIB") (part "RES 10K 0603 - SMD"))
    )
    (comp (ref "R9")
      (value "10K")
      (footprint "AR_0603_R")
      (description "RES 10K 0603 - SMD")
      (fields (field (name "PUBLISHER") "Altium Limited"))
      (libsource (lib "LIB") (part "RES 10K 0603 - SMD"))
    )
    (comp (ref "R10")
      (value "10K")
      (footprint "AR_0603_R")
      (description "RES 10K 0603 - SMD")
      (fields (field (name "PUBLISHER") "Altium Limited"))
      (libsource (lib "LIB") (part "RES 10K 0603 - SMD"))
    )
    (comp (ref "R11")
      (value "10K")
      (footprint "AR_0603_R")
      (description "RES 10K 0603 - SMD")
      (fields (field (name "PUBLISHER") "Altium Limited"))
      (libsource (lib "LIB") (part "RES 10K 0603 - SMD"))
    )
    (comp (ref "R12")
      (value "10K")
      (footprint "AR_0603_R")
      (description "RES 10K 0603 - SMD")
      (fields (field (name "PUBLISHER") "Altium Limited"))
      (libsource (lib "LIB") (part "RES 10K 0603 - SMD"))
    )
    (comp (ref "R13")
      (value "10K")
      (footprint "AR_0603_R")
      (description "RES 10K 0603 - SMD")
      (fields (field (name "PUBLISHER") "Altium Limited"))
      (libsource (lib "LIB") (part "RES 10K 0603 - SMD"))
    )
    (comp (ref "R14")
      (value "10K")
      (footprint "AR_0603_R")
      (description "RES 10K 0603 - SMD")
      (fields (field (name "PUBLISHER") "Altium Limited"))
      (libsource (lib "LIB") (part "RES 10K 0603 - SMD"))
    )
    (comp (ref "R15")
      (value "470R")
      (footprint "AR_0603_R")
      (description "RES 470R 0603 - SMD")
      (fields (field (name "PUBLISHER") "Altium Limited"))
      (libsource (lib "LIB") (part "RES 470R 0603 - SMD"))
    )
    (comp (ref "R16")
      (value "10K")
      (footprint "AR_0603_R")
      (description "RES 10K 0603 - SMD")
      (fields (field (name "PUBLISHER") "Altium Limited"))
      (libsource (lib "LIB") (part "RES 10K 0603 - SMD"))
    )
    (comp (ref "R17")
      (value "10K")
      (footprint "AR_0603_R")
      (description "RES 10K 0603 - SMD")
      (fields (field (name "PUBLISHER") "Altium Limited"))
      (libsource (lib "LIB") (part "RES 10K 0603 - SMD"))
    )
    (comp (ref "R18")
      (value "10K")
      (footprint "AR_0603_R")
      (description "RES 10K 0603 - SMD")
      (fields (field (name "PUBLISHER") "Altium Limited"))
      (libsource (lib "LIB") (part "RES 10K 0603 - SMD"))
    )
    (comp (ref "R19")
      (value "470R")
      (footprint "AR_0603_R")
      (description "RES 470R 0603 - SMD")
      (fields (field (name "PUBLISHER") "Altium Limited"))
      (libsource (lib "LIB") (part "RES 470R 0603 - SMD"))
    )
    (comp (ref "R20")
      (value "470R")
      (footprint "AR_0603_R")
      (description "RES 470R 0603 - SMD")
      (fields (field (name "PUBLISHER") "Altium Limited"))
      (libsource (lib "LIB") (part "RES 470R 0603 - SMD"))
    )
    (comp (ref "R21")
      (value "470R")
      (footprint "AR_0603_R")
      (description "RES 470R 0603 - SMD")
      (fields (field (name "PUBLISHER") "Altium Limited"))
      (libsource (lib "LIB") (part "RES 470R 0603 - SMD"))
    )
    (comp (ref "R22")
      (value "470R")
      (footprint "AR_0603_R")
      (description "RES 470R 0603 - SMD")
      (fields (field (name "PUBLISHER") "Altium Limited"))
      (libsource (lib "LIB") (part "RES 470R 0603 - SMD"))
    )
    (comp (ref "R23")
      (value "10K")
      (footprint "AR_0603_R")
      (description "RES 10K 0603 - SMD")
      (fields (field (name "PUBLISHER") "Altium Limited"))
      (libsource (lib "LIB") (part "RES 10K 0603 - SMD"))
    )
    (comp (ref "R24")
      (value "10K")
      (footprint "AR_0603_R")
      (description "RES 10K 0603 - SMD")
      (fields (field (name "PUBLISHER") "Altium Limited"))
      (libsource (lib "LIB") (part "RES 10K 0603 - SMD"))
    )
    (comp (ref "R25")
      (value "10K")
      (footprint "AR_0603_R")
      (description "RES 10K 0603 - SMD")
      (fields (field (name "PUBLISHER") "Altium Limited"))
      (libsource (lib "LIB") (part "RES 10K 0603 - SMD"))
    )
    (comp (ref "R26")
      (value "10K")
      (footprint "AR_0603_R")
      (description "RES 10K 0603 - SMD")
      (fields (field (name "PUBLISHER") "Altium Limited"))
      (libsource (lib "LIB") (part "RES 10K 0603 - SMD"))
    )
    (comp (ref "R27")
      (value "1K")
      (footprint "AR_0603_R")
      (description "RES 1K 0603 - SMD")
      (fields (field (name "PUBLISHER") "Altium Limited"))
      (libsource (lib "LIB") (part "RES 1K 0603 - SMD"))
    )
    (comp (ref "R28")
      (value "10K")
      (footprint "R20")
      (description "RES 10K 1/8W - PTH")
      (fields (field (name "PUBLISHER") "Altium Limited"))
      (libsource (lib "") (part "RES 10K 1/8W - PTH_1"))
    )
    (comp (ref "R36")
      (value "330R")
      (footprint "R20")
      (description "RES 330R 1/8W - PTH")
      (fields (field (name "Comment") "4K7") (field (name "PUBLISHER") "Altium Limited"))
      (libsource (lib "LIB") (part "RES 330R 1/8W - PTH"))
    )
    (comp (ref "R37")
      (value "330R")
      (footprint "R20")
      (description "RES 330R 1/8W - PTH")
      (fields (field (name "Comment") "4K7") (field (name "PUBLISHER") "Altium Limited"))
      (libsource (lib "LIB") (part "RES 330R 1/8W - PTH"))
    )
    (comp (ref "R38")
      (value "4K7")
      (footprint "R20")
      (description "RES 4K7 1/8W - PTH")
      (fields (field (name "PUBLISHER") "Altium Limited"))
      (libsource (lib "LIB") (part "RES 4K7 1/8W - PTH"))
    )
    (comp (ref "R40")
      (value "1K")
      (footprint "R20")
      (description "RES 1K 1/8W - PTH")
      (fields (field (name "PUBLISHER") "Altium Limited"))
      (libsource (lib "LIB") (part "RES 1K 1/8W - PTH"))
    )
    (comp (ref "R42")
      (value "4K7")
      (footprint "R20")
      (description "RES 4K7 1/8W - PTH")
      (fields (field (name "PUBLISHER") "Altium Limited"))
      (libsource (lib "LIB") (part "RES 4K7 1/8W - PTH"))
    )
    (comp (ref "R43")
      (value "330R")
      (footprint "R20")
      (description "RES 330R 1/8W - PTH")
      (fields (field (name "Comment") "4K7") (field (name "PUBLISHER") "Altium Limited"))
      (libsource (lib "LIB") (part "RES 330R 1/8W - PTH"))
    )
    (comp (ref "R45")
      (value "10K")
      (footprint "R20")
      (description "RES 10K 1/8W - PTH")
      (fields (field (name "PUBLISHER") "Altium Limited"))
      (libsource (lib "LIB") (part "RES 10K 1/8W - PTH"))
    )
    (comp (ref "R46")
      (value "4K7")
      (footprint "R20")
      (description "RES 4K7 1/8W - PTH")
      (fields (field (name "PUBLISHER") "Altium Limited"))
      (libsource (lib "LIB") (part "RES 4K7 1/8W - PTH"))
    )
    (comp (ref "R47")
      (value "1K")
      (footprint "R20")
      (description "RES 1K 1/8W - PTH")
      (fields (field (name "PUBLISHER") "Altium Limited"))
      (libsource (lib "LIB") (part "RES 1K 1/8W - PTH"))
    )
    (comp (ref "R48")
      (value "1K")
      (footprint "R20")
      (description "RES 1K 1/8W - PTH")
      (fields (field (name "PUBLISHER") "Altium Limited"))
      (libsource (lib "LIB") (part "RES 1K 1/8W - PTH"))
    )
    (comp (ref "R49")
      (value "4K7")
      (footprint "R20")
      (description "RES 4K7 1/8W - PTH")
      (fields (field (name "PUBLISHER") "Altium Limited"))
      (libsource (lib "LIB") (part "RES 4K7 1/8W - PTH"))
    )
    (comp (ref "R50")
      (value "330R")
      (footprint "R20")
      (description "RES 330R 1/8W - PTH")
      (fields (field (name "Comment") "4K7") (field (name "PUBLISHER") "Altium Limited"))
      (libsource (lib "LIB") (part "RES 330R 1/8W - PTH"))
    )
    (comp (ref "R51")
      (value "330R")
      (footprint "R20")
      (description "RES 330R 1/8W - PTH")
      (fields (field (name "Comment") "4K7") (field (name "PUBLISHER") "Altium Limited"))
      (libsource (lib "LIB") (part "RES 330R 1/8W - PTH"))
    )
    (comp (ref "R52")
      (value "10K")
      (footprint "POT_G")
      (description "Potenciometro 10K Bourns")
      (fields (field (name "PUBLISHER") "Altium Limited"))
      (libsource (lib "LIB") (part "Potenciometro 10K Bourns"))
    )
    (comp (ref "R53")
      (value "1K")
      (footprint "R20")
      (description "RES 1K 1/8W - PTH")
      (fields (field (name "PUBLISHER") "Altium Limited"))
      (libsource (lib "LIB") (part "RES 1K 1/8W - PTH"))
    )
    (comp (ref "R54")
      (value "1K")
      (footprint "R20")
      (description "RES 1K 1/8W - PTH")
      (fields (field (name "PUBLISHER") "Altium Limited"))
      (libsource (lib "LIB") (part "RES 1K 1/8W - PTH"))
    )
    (comp (ref "R55")
      (value "4K7")
      (footprint "R20")
      (description "RES 4K7 1/8W - PTH")
      (fields (field (name "PUBLISHER") "Altium Limited"))
      (libsource (lib "LIB") (part "RES 4K7 1/8W - PTH"))
    )
    (comp (ref "R56")
      (value "1K")
      (footprint "R20")
      (description "RES 1K 1/8W - PTH")
      (fields (field (name "PUBLISHER") "Altium Limited"))
      (libsource (lib "LIB") (part "RES 1K 1/8W - PTH"))
    )
    (comp (ref "R57")
      (value "4K7")
      (footprint "R20")
      (description "RES 4K7 1/8W - PTH")
      (fields (field (name "PUBLISHER") "Altium Limited"))
      (libsource (lib "LIB") (part "RES 4K7 1/8W - PTH"))
    )
    (comp (ref "R58")
      (value "1K")
      (footprint "R20")
      (description "RES 1K 1/8W - PTH")
      (fields (field (name "PUBLISHER") "Altium Limited"))
      (libsource (lib "LIB") (part "RES 1K 1/8W - PTH"))
    )
    (comp (ref "R59")
      (value "1K")
      (footprint "R20")
      (description "RES 1K 1/8W - PTH")
      (fields (field (name "PUBLISHER") "Altium Limited"))
      (libsource (lib "LIB") (part "RES 1K 1/8W - PTH"))
    )
    (comp (ref "R60")
      (value "1K")
      (footprint "R20")
      (description "RES 1K 1/8W - PTH")
      (fields (field (name "PUBLISHER") "Altium Limited"))
      (libsource (lib "LIB") (part "RES 1K 1/8W - PTH"))
    )
    (comp (ref "R61")
      (value "4K7")
      (footprint "R20")
      (description "RES 4K7 1/8W - PTH")
      (fields (field (name "PUBLISHER") "Altium Limited"))
      (libsource (lib "LIB") (part "RES 4K7 1/8W - PTH"))
    )
    (comp (ref "R62")
      (value "1K")
      (footprint "R20")
      (description "RES 1K 1/8W - PTH")
      (fields (field (name "PUBLISHER") "Altium Limited"))
      (libsource (lib "LIB") (part "RES 1K 1/8W - PTH"))
    )
    (comp (ref "R63")
      (value "4K7")
      (footprint "R20")
      (description "RES 4K7 1/8W - PTH")
      (fields (field (name "PUBLISHER") "Altium Limited"))
      (libsource (lib "LIB") (part "RES 4K7 1/8W - PTH"))
    )
    (comp (ref "R64")
      (value "1K")
      (footprint "R20")
      (description "RES 1K 1/8W - PTH")
      (fields (field (name "PUBLISHER") "Altium Limited"))
      (libsource (lib "LIB") (part "RES 1K 1/8W - PTH"))
    )
    (comp (ref "R65")
      (value "470R")
      (footprint "R20")
      (description "RES 470R 1/8W - PTH")
      (fields (field (name "Comment") "4K7") (field (name "PUBLISHER") "Altium Limited"))
      (libsource (lib "LIB") (part "RES 470R 1/8W - PTH"))
    )
    (comp (ref "R67")
      (value "1K")
      (footprint "R20")
      (description "RES 1K 1/8W - PTH")
      (fields (field (name "PUBLISHER") "Altium Limited"))
      (libsource (lib "LIB") (part "RES 1K 1/8W - PTH"))
    )
    (comp (ref "R69")
      (value "1K")
      (footprint "R20")
      (description "RES 1K 1/8W - PTH")
      (fields (field (name "PUBLISHER") "Altium Limited"))
      (libsource (lib "LIB") (part "RES 1K 1/8W - PTH"))
    )
    (comp (ref "R70")
      (value "270R")
      (footprint "R20")
      (description "RES 270R 1/8W - PTH")
      (fields (field (name "Comment") "4K7") (field (name "PUBLISHER") "Altium Limited"))
      (libsource (lib "LIB") (part "RES 270R 1/8W - PTH"))
    )
    (comp (ref "R71")
      (value "270R")
      (footprint "R20")
      (description "RES 270R 1/8W - PTH")
      (fields (field (name "Comment") "4K7") (field (name "PUBLISHER") "Altium Limited"))
      (libsource (lib "LIB") (part "RES 270R 1/8W - PTH"))
    )
    (comp (ref "R72")
      (value "1K2")
      (footprint "R20")
      (description "RES 1K2 1/8W - PTH")
      (fields (field (name "Comment") "4K7") (field (name "PUBLISHER") "Altium Limited"))
      (libsource (lib "LIB") (part "RES 1K2 1/8W - PTH"))
    )
    (comp (ref "R73")
      (value "1K2")
      (footprint "R20")
      (description "RES 1K2 1/8W - PTH")
      (fields (field (name "Comment") "4K7") (field (name "PUBLISHER") "Altium Limited"))
      (libsource (lib "LIB") (part "RES 1K2 1/8W - PTH"))
    )
    (comp (ref "R74")
      (value "1K")
      (footprint "R20")
      (description "RES 1K 1/8W - PTH")
      (fields (field (name "PUBLISHER") "Altium Limited"))
      (libsource (lib "LIB") (part "RES 1K 1/8W - PTH"))
    )
    (comp (ref "R75")
      (value "1K")
      (footprint "R20")
      (description "RES 1K 1/8W - PTH")
      (fields (field (name "PUBLISHER") "Altium Limited"))
      (libsource (lib "LIB") (part "RES 1K 1/8W - PTH"))
    )
    (comp (ref "R76")
      (value "1K2")
      (footprint "R20")
      (description "RES 1K2 1/8W - PTH")
      (fields (field (name "Comment") "4K7") (field (name "PUBLISHER") "Altium Limited"))
      (libsource (lib "LIB") (part "RES 1K2 1/8W - PTH"))
    )
    (comp (ref "R77")
      (value "1K2")
      (footprint "R20")
      (description "RES 1K2 1/8W - PTH")
      (fields (field (name "Comment") "4K7") (field (name "PUBLISHER") "Altium Limited"))
      (libsource (lib "LIB") (part "RES 1K2 1/8W - PTH"))
    )
    (comp (ref "R79")
      (value "1K")
      (footprint "R20")
      (description "RES 1K 1/8W - PTH")
      (fields (field (name "PUBLISHER") "Altium Limited"))
      (libsource (lib "LIB") (part "RES 1K 1/8W - PTH"))
    )
    (comp (ref "R80")
      (value "270R")
      (footprint "R20")
      (description "RES 270R 1/8W - PTH")
      (fields (field (name "Comment") "4K7") (field (name "PUBLISHER") "Altium Limited"))
      (libsource (lib "LIB") (part "RES 270R 1/8W - PTH"))
    )
    (comp (ref "R81")
      (value "270R")
      (footprint "R20")
      (description "RES 270R 1/8W - PTH")
      (fields (field (name "Comment") "4K7") (field (name "PUBLISHER") "Altium Limited"))
      (libsource (lib "LIB") (part "RES 270R 1/8W - PTH"))
    )
    (comp (ref "R83")
      (value "1K2")
      (footprint "R20")
      (description "RES 1K2 1/8W - PTH")
      (fields (field (name "Comment") "4K7") (field (name "PUBLISHER") "Altium Limited"))
      (libsource (lib "LIB") (part "RES 1K2 1/8W - PTH"))
    )
    (comp (ref "R84")
      (value "1K")
      (footprint "R20")
      (description "RES 1K 1/8W - PTH")
      (fields (field (name "PUBLISHER") "Altium Limited"))
      (libsource (lib "LIB") (part "RES 1K 1/8W - PTH"))
    )
    (comp (ref "R85")
      (value "1K2")
      (footprint "R20")
      (description "RES 1K2 1/8W - PTH")
      (fields (field (name "Comment") "4K7") (field (name "PUBLISHER") "Altium Limited"))
      (libsource (lib "LIB") (part "RES 1K2 1/8W - PTH"))
    )
    (comp (ref "R86")
      (value "1K")
      (footprint "R20")
      (description "RES 1K 1/8W - PTH")
      (fields (field (name "PUBLISHER") "Altium Limited"))
      (libsource (lib "LIB") (part "RES 1K 1/8W - PTH"))
    )
    (comp (ref "R87")
      (value "1K2")
      (footprint "R20")
      (description "RES 1K2 1/8W - PTH")
      (fields (field (name "Comment") "4K7") (field (name "PUBLISHER") "Altium Limited"))
      (libsource (lib "LIB") (part "RES 1K2 1/8W - PTH"))
    )
    (comp (ref "R88")
      (value "1K2")
      (footprint "R20")
      (description "RES 1K2 1/8W - PTH")
      (fields (field (name "Comment") "4K7") (field (name "PUBLISHER") "Altium Limited"))
      (libsource (lib "LIB") (part "RES 1K2 1/8W - PTH"))
    )
    (comp (ref "R89")
      (value "270R")
      (footprint "R20")
      (description "RES 270R 1/8W - PTH")
      (fields (field (name "Comment") "4K7") (field (name "PUBLISHER") "Altium Limited"))
      (libsource (lib "LIB") (part "RES 270R 1/8W - PTH"))
    )
    (comp (ref "R90")
      (value "270R")
      (footprint "R20")
      (description "RES 270R 1/8W - PTH")
      (fields (field (name "Comment") "4K7") (field (name "PUBLISHER") "Altium Limited"))
      (libsource (lib "LIB") (part "RES 270R 1/8W - PTH"))
    )
    (comp (ref "R91")
      (value "1K2")
      (footprint "R20")
      (description "RES 1K2 1/8W - PTH")
      (fields (field (name "Comment") "4K7") (field (name "PUBLISHER") "Altium Limited"))
      (libsource (lib "LIB") (part "RES 1K2 1/8W - PTH"))
    )
    (comp (ref "R92")
      (value "1K")
      (footprint "R20")
      (description "RES 1K 1/8W - PTH")
      (fields (field (name "PUBLISHER") "Altium Limited"))
      (libsource (lib "LIB") (part "RES 1K 1/8W - PTH"))
    )
    (comp (ref "R93")
      (value "1K2")
      (footprint "R20")
      (description "RES 1K2 1/8W - PTH")
      (fields (field (name "Comment") "4K7") (field (name "PUBLISHER") "Altium Limited"))
      (libsource (lib "LIB") (part "RES 1K2 1/8W - PTH"))
    )
    (comp (ref "R94")
      (value "1K")
      (footprint "R20")
      (description "RES 1K 1/8W - PTH")
      (fields (field (name "PUBLISHER") "Altium Limited"))
      (libsource (lib "LIB") (part "RES 1K 1/8W - PTH"))
    )
    (comp (ref "R95")
      (value "1K2")
      (footprint "R20")
      (description "RES 1K2 1/8W - PTH")
      (fields (field (name "Comment") "4K7") (field (name "PUBLISHER") "Altium Limited"))
      (libsource (lib "LIB") (part "RES 1K2 1/8W - PTH"))
    )
    (comp (ref "R96")
      (value "1K2")
      (footprint "R20")
      (description "RES 1K2 1/8W - PTH")
      (fields (field (name "Comment") "4K7") (field (name "PUBLISHER") "Altium Limited"))
      (libsource (lib "LIB") (part "RES 1K2 1/8W - PTH"))
    )
    (comp (ref "R97")
      (value "330R")
      (footprint "R20")
      (description "RES 330R 1/8W - PTH")
      (fields (field (name "Comment") "4K7") (field (name "PUBLISHER") "Altium Limited"))
      (libsource (lib "LIB") (part "RES 330R 1/8W - PTH"))
    )
    (comp (ref "R98")
      (value "330R")
      (footprint "R20")
      (description "RES 330R 1/8W - PTH")
      (fields (field (name "Comment") "4K7") (field (name "PUBLISHER") "Altium Limited"))
      (libsource (lib "LIB") (part "RES 330R 1/8W - PTH"))
    )
    (comp (ref "R99")
      (value "180R")
      (footprint "R20")
      (description "RES 180R 1/8W - PTH")
      (fields (field (name "PUBLISHER") "Altium Limited"))
      (libsource (lib "LIB") (part "RES 180R 1/8W - PTH"))
    )
    (comp (ref "R100")
      (value "330R")
      (footprint "R20")
      (description "RES 330R 1/8W - PTH")
      (fields (field (name "Comment") "4K7") (field (name "PUBLISHER") "Altium Limited"))
      (libsource (lib "LIB") (part "RES 330R 1/8W - PTH"))
    )
    (comp (ref "R101")
      (value "10K")
      (footprint "R20")
      (description "RES 10K 1/8W - PTH")
      (fields (field (name "PUBLISHER") "Altium Limited"))
      (libsource (lib "LIB") (part "RES 10K 1/8W - PTH"))
    )
    (comp (ref "R102")
      (value "330R")
      (footprint "R20")
      (description "RES 330R 1/8W - PTH")
      (fields (field (name "Comment") "4K7") (field (name "PUBLISHER") "Altium Limited"))
      (libsource (lib "LIB") (part "RES 330R 1/8W - PTH"))
    )
    (comp (ref "RV1")
      (value "VRS")
      (footprint "0402_MOV")
      (description "VARISTOR 0402 - SMD")
      (fields (field (name "PUBLISHER") "Altium Limited"))
      (libsource (lib "LIB") (part "VARISTOR 0402 - SMD"))
    )
    (comp (ref "RV2")
      (value "VRS")
      (footprint "0402_MOV")
      (description "VARISTOR 0402 - SMD")
      (fields (field (name "PUBLISHER") "Altium Limited"))
      (libsource (lib "LIB") (part "VARISTOR 0402 - SMD"))
    )
    (comp (ref "RV3")
      (value "VRS")
      (footprint "0402_MOV")
      (description "VARISTOR 0402 - SMD")
      (fields (field (name "PUBLISHER") "Altium Limited"))
      (libsource (lib "LIB") (part "VARISTOR 0402 - SMD"))
    )
    (comp (ref "RV4")
      (value "VRS")
      (footprint "0402_MOV")
      (description "VARISTOR 0402 - SMD")
      (fields (field (name "PUBLISHER") "Altium Limited"))
      (libsource (lib "LIB") (part "VARISTOR 0402 - SMD"))
    )
    (comp (ref "S1")
      (value "CH_TACT")
      (footprint "PUSH")
      (description "CHAVE TACTIL RIGHT")
      (fields (field (name "PUBLISHER") "Altium Limited"))
      (libsource (lib "LIB") (part "CHAVE TACTIL RIGHT"))
    )
    (comp (ref "T1")
      (value "Trans3")
      (footprint "TRF_6")
      (description "Three-winding Transformer (Non-Ideal)")
      (fields (field (name "PUBLISHER") "Altium Limited"))
      (libsource (lib "LIB") (part "Trans3"))
    )
    (comp (ref "TFLASH1")
      (value "CON SD")
      (footprint "MEM2060")
      (description "MICRO SD MEMORY CARD CONNECTOR PUSH-PUSH SMT, CARD ENTRY NORMAL 1,90MM PROFILE - MOLEX MEN2060")
      (fields (field (name "PUBLISHER") "Altium Limited"))
      (libsource (lib "LIB") (part "CON SD CARD MEN2060 - MOLEX"))
    )
    (comp (ref "U1")
      (value "PIC24FJ256GB106-I/PT")
      (footprint "AR_TQFP64")
      (fields (field (name "PUBLISHER") "Altium Limited"))
      (libsource (lib "LIB") (part "PIC24FJ256GB106-I/PT"))
    )
    (comp (ref "U2")
      (value "SOIC8")
      (footprint "AR_SO8")
      (fields (field (name "PUBLISHER") "Altium Limited"))
      (libsource (lib "LIB") (part "SOIC8"))
    )
    (comp (ref "U3")
      (value "MRF24WB0MX")
      (footprint "MRF24WB0MA")
      (description "2.4 GHz, IEEE Std. 802.11b RF Transceiver Module")
      (libsource (lib "LIB") (part "MRF24WB0MX"))
    )
    (comp (ref "U4")
      (value "PRTR5V0U2X/SOT143B")
      (footprint "SOT143B")
      (description "Voltage Supervisor with Manual Reset Input, 4-Pin SOT-143, PRTR5V0U2X/SOT143B")
      (libsource (lib "LIB") (part "PRTR5V0U2X/SOT143B"))
    )
    (comp (ref "U5")
      (value "LM317AEMP")
      (footprint "SOT223")
      (description "3-Terminal Adjustable Regulator")
      (fields
        (field (name "MANUFACTURER") "National Semiconductor")
        (field (name "DIGIKEYPARTNUMBER") "LM317AEMPCT-ND")
        (field (name "PUBLISHER") "Altium Limited")
      )
      (libsource (lib "LIB") (part "LM317AEMP"))
    )
    (comp (ref "U6")
      (value "PIC16F1503-I/P")
      (footprint "DIP14")
      (fields (field (name "PUBLISHER") "Altium Limited"))
      (libsource (lib "LIB") (part "PIC16F1503-I/P"))
    )
    (comp (ref "U7")
      (value "PS2501-A")
      (footprint "DIP-4")
      (description "CI OPTO ACOPLADOR PS25010-A")
      (fields (field (name "PUBLISHER") "Altium Limited"))
      (libsource (lib "LIB") (part "CI OPTO ACOPLADOR PS25010-A"))
    )
    (comp (ref "U8")
      (value "PIC16F77-I/P")
      (footprint "DIP40")
      (fields (field (name "PUBLISHER") "Altium Limited"))
      (libsource (lib "LIB") (part "PIC16F77-I/P"))
    )
    (comp (ref "U9")
      (value "PS2501-A")
      (footprint "DIP-4")
      (description "CI OPTO ACOPLADOR PS25010-A")
      (fields (field (name "PUBLISHER") "Altium Limited"))
      (libsource (lib "LIB") (part "CI OPTO ACOPLADOR PS25010-A"))
    )
    (comp (ref "U10")
      (value "PS2501-A")
      (footprint "DIP-4")
      (description "CI OPTO ACOPLADOR PS25010-A")
      (fields (field (name "PUBLISHER") "Altium Limited"))
      (libsource (lib "LIB") (part "CI OPTO ACOPLADOR PS25010-A"))
    )
    (comp (ref "U11")
      (value "LM7805")
      (footprint "TO220")
      (description "CI LM7805")
      (fields (field (name "PUBLISHER") "Altium Limited"))
      (libsource (lib "LIB") (part "CI LM7805"))
    )
    (comp (ref "U12")
      (value "PS2501-A")
      (footprint "DIP-4")
      (description "CI OPTO ACOPLADOR PS25010-A")
      (fields (field (name "PUBLISHER") "Altium Limited"))
      (libsource (lib "LIB") (part "CI OPTO ACOPLADOR PS25010-A"))
    )
    (comp (ref "U13")
      (value "LM7812")
      (footprint "TO220")
      (description "CI LM7812")
      (fields (field (name "PUBLISHER") "Altium Limited"))
      (libsource (lib "LIB") (part "CI LM7812"))
    )
    (comp (ref "U14")
      (value "PS2501-A")
      (footprint "DIP-4")
      (description "CI OPTO ACOPLADOR PS25010-A")
      (fields (field (name "PUBLISHER") "Altium Limited"))
      (libsource (lib "LIB") (part "CI OPTO ACOPLADOR PS25010-A"))
    )
    (comp (ref "U15")
      (value "PS2501-A")
      (footprint "DIP-4")
      (description "CI OPTO ACOPLADOR PS25010-A")
      (fields (field (name "PUBLISHER") "Altium Limited"))
      (libsource (lib "LIB") (part "CI OPTO ACOPLADOR PS25010-A"))
    )
    (comp (ref "U16")
      (value "LM7824")
      (footprint "TO220")
      (description "CI LM7824")
      (fields (field (name "PUBLISHER") "Altium Limited"))
      (libsource (lib "LIB") (part "CI LM7824"))
    )
    (comp (ref "U17")
      (value "PS2501-A")
      (footprint "DIP-4")
      (description "CI OPTO ACOPLADOR PS25010-A")
      (fields (field (name "PUBLISHER") "Altium Limited"))
      (libsource (lib "LIB") (part "CI OPTO ACOPLADOR PS25010-A"))
    )
    (comp (ref "U18")
      (value "PS2501-A")
      (footprint "DIP-4")
      (description "CI OPTO ACOPLADOR PS25010-A")
      (fields (field (name "PUBLISHER") "Altium Limited"))
      (libsource (lib "LIB") (part "CI OPTO ACOPLADOR PS25010-A"))
    )
    (comp (ref "U19")
      (value "LM7812")
      (footprint "TO220")
      (description "CI LM7812")
      (fields (field (name "PUBLISHER") "Altium Limited"))
      (libsource (lib "LIB") (part "CI LM7812"))
    )
    (comp (ref "U20")
      (value "LM7805")
      (footprint "TO220")
      (description "CI LM7805")
      (fields (field (name "PUBLISHER") "Altium Limited"))
      (libsource (lib "LIB") (part "CI LM7805"))
    )
    (comp (ref "U21")
      (value "PS2501-A")
      (footprint "DIP-4")
      (description "CI OPTO ACOPLADOR PS25010-A")
      (fields (field (name "PUBLISHER") "Altium Limited"))
      (libsource (lib "LIB") (part "CI OPTO ACOPLADOR PS25010-A"))
    )
    (comp (ref "U22")
      (value "PS2501-A")
      (footprint "DIP-4")
      (description "CI OPTO ACOPLADOR PS25010-A")
      (fields (field (name "PUBLISHER") "Altium Limited"))
      (libsource (lib "LIB") (part "CI OPTO ACOPLADOR PS25010-A"))
    )
    (comp (ref "Y1")
      (value "20MHz")
      (footprint "XTAL_SMD_KX6")
      (description "CRISTAL OC. 20MHz")
      (fields (field (name "PUBLISHER") "Altium Limited"))
      (libsource (lib "LIB") (part "XTAL"))
    )
    (comp (ref "Y2")
      (value "20MHz")
      (footprint "XTAL")
      (description "CRISTAL OCIL. 20MHz")
      (fields (field (name "PUBLISHER") "Altium Limited"))
      (libsource (lib "LIB") (part "CRISTAL OCIL. 20MHz"))
    )
  )
  (nets
    (net (code "1") (name "+3.3V") (class "Default")
      (node (ref "C10") (pin "2") (pinfunction "2_2") (pintype "passive"))
      (node (ref "C12") (pin "2") (pinfunction "2_2") (pintype "passive"))
      (node (ref "C13") (pin "2") (pinfunction "2_2") (pintype "passive"))
      (node (ref "C14") (pin "2") (pinfunction "2_2") (pintype "passive"))
      (node (ref "C16") (pin "2") (pinfunction "2_2") (pintype "passive"))
      (node (ref "C19") (pin "2") (pinfunction "2_2") (pintype "passive"))
      (node (ref "C5") (pin "2") (pinfunction "2_2") (pintype "passive"))
      (node (ref "C6") (pin "2") (pinfunction "2_2") (pintype "passive"))
      (node (ref "C7") (pin "2") (pinfunction "2_2") (pintype "passive"))
      (node (ref "C8") (pin "2") (pinfunction "2_2") (pintype "passive"))
      (node (ref "C9") (pin "2") (pinfunction "2_2") (pintype "passive"))
      (node (ref "D2") (pin "1") (pinfunction "A_1") (pintype "passive"))
      (node (ref "D3") (pin "1") (pinfunction "A_1") (pintype "passive"))
      (node (ref "D4") (pin "1") (pinfunction "A_1") (pintype "passive"))
      (node (ref "D5") (pin "1") (pinfunction "A_1") (pintype "passive"))
      (node (ref "D6") (pin "1") (pinfunction "A_1") (pintype "passive"))
      (node (ref "J1") (pin "2") (pinfunction "2_2") (pintype "passive"))
      (node (ref "R1") (pin "2") (pinfunction "2_2") (pintype "passive"))
      (node (ref "R10") (pin "1") (pinfunction "1_1") (pintype "passive"))
      (node (ref "R11") (pin "1") (pinfunction "1_1") (pintype "passive"))
      (node (ref "R12") (pin "1") (pinfunction "1_1") (pintype "passive"))
      (node (ref "R13") (pin "2") (pinfunction "2_2") (pintype "passive"))
      (node (ref "R16") (pin "2") (pinfunction "2_2") (pintype "passive"))
      (node (ref "R17") (pin "2") (pinfunction "2_2") (pintype "passive"))
      (node (ref "R18") (pin "2") (pinfunction "2_2") (pintype "passive"))
      (node (ref "R23") (pin "2") (pinfunction "2_2") (pintype "passive"))
      (node (ref "R27") (pin "2") (pinfunction "2_2") (pintype "passive"))
      (node (ref "R3") (pin "2") (pinfunction "2_2") (pintype "passive"))
      (node (ref "R9") (pin "2") (pinfunction "2_2") (pintype "passive"))
      (node (ref "TFLASH1") (pin "P4") (pinfunction "VDD_P4") (pintype "passive"))
      (node (ref "U1") (pin "10") (pinfunction "VDD_10") (pintype "power_in"))
      (node (ref "U1") (pin "19") (pinfunction "AVDD_19") (pintype "power_in"))
      (node (ref "U1") (pin "26") (pinfunction "VDD_26") (pintype "power_in"))
      (node (ref "U1") (pin "35") (pinfunction "VUSB_35") (pintype "power_in"))
      (node (ref "U1") (pin "38") (pinfunction "VDD_38") (pintype "power_in"))
      (node (ref "U1") (pin "57") (pinfunction "ENVREG_57") (pintype "input"))
      (node (ref "U2") (pin "7") (pinfunction "HOLD_7") (pintype "power_in"))
      (node (ref "U2") (pin "8") (pinfunction "VCC_8") (pintype "power_in"))
      (node (ref "U3") (pin "17") (pinfunction "VDD_17") (pintype "power_in"))
      (node (ref "U3") (pin "29") (pinfunction "VDD_29") (pintype "power_in"))
      (node (ref "U5") (pin "2") (pinfunction "OUT_2") (pintype "power_in"))
      (node (ref "U5") (pin "4") (pinfunction "TAB_4") (pintype "power_in"))
    )
    (net (code "2") (name "+5V") (class "Default")
      (node (ref "C46") (pin "2") (pinfunction "2_2") (pintype "passive"))
      (node (ref "C47") (pin "2") (pinfunction "2_2") (pintype "passive"))
      (node (ref "D16") (pin "1") (pinfunction "A_1") (pintype "passive"))
      (node (ref "J4") (pin "2") (pinfunction "2_2") (pintype "passive"))
      (node (ref "J5") (pin "1") (pinfunction "VBUS_1") (pintype "power_in"))
      (node (ref "J8") (pin "8") (pinfunction "8_8") (pintype "passive"))
      (node (ref "J9") (pin "2") (pinfunction "2_2") (pintype "passive"))
      (node (ref "LCD1") (pin "16") (pinfunction "K_16") (pintype "power_in"))
      (node (ref "LCD1") (pin "2") (pinfunction "VDD_2") (pintype "power_in"))
      (node (ref "R28") (pin "2") (pinfunction "2_2") (pintype "passive"))
      (node (ref "R45") (pin "2") (pinfunction "2_2") (pintype "passive"))
      (node (ref "R52") (pin "1") (pinfunction "TOP_1") (pintype "passive"))
      (node (ref "R70") (pin "2") (pinfunction "2_2") (pintype "passive"))
      (node (ref "R71") (pin "2") (pinfunction "2_2") (pintype "passive"))
      (node (ref "R80") (pin "2") (pinfunction "2_2") (pintype "passive"))
      (node (ref "R81") (pin "2") (pinfunction "2_2") (pintype "passive"))
      (node (ref "R89") (pin "2") (pinfunction "2_2") (pintype "passive"))
      (node (ref "R90") (pin "2") (pinfunction "2_2") (pintype "passive"))
      (node (ref "U20") (pin "3") (pinfunction "OUT_3") (pintype "power_in"))
      (node (ref "U22") (pin "4") (pinfunction "C_4") (pintype "passive"))
      (node (ref "U8") (pin "11") (pinfunction "VDD_11") (pintype "power_in"))
      (node (ref "U8") (pin "32") (pinfunction "VDD_32") (pintype "power_in"))
      (node (ref "U9") (pin "4") (pinfunction "C_4") (pintype "passive"))
    )
    (net (code "3") (name "+5V_USB") (class "Default")
      (node (ref "C17") (pin "2") (pinfunction "2_2") (pintype "passive"))
      (node (ref "C18") (pin "2") (pinfunction "2_2") (pintype "passive"))
      (node (ref "D1") (pin "3") (pinfunction "K_3") (pintype "passive"))
      (node (ref "J3") (pin "1") (pinfunction "VBUS_1") (pintype "power_in"))
      (node (ref "U1") (pin "34") (pinfunction "VBUS_34") (pintype "power_in"))
      (node (ref "U4") (pin "4") (pinfunction "VCC_4") (pintype "power_in"))
      (node (ref "U5") (pin "3") (pinfunction "IN_3") (pintype "power_in"))
    )
    (net (code "4") (name "+5_ISOL") (class "Default")
      (node (ref "C24") (pin "2") (pinfunction "2_2") (pintype "passive"))
      (node (ref "C25") (pin "2") (pinfunction "2_2") (pintype "passive"))
      (node (ref "J6") (pin "2") (pinfunction "2_2") (pintype "passive"))
      (node (ref "R101") (pin "1") (pinfunction "1_1") (pintype "passive"))
      (node (ref "U11") (pin "3") (pinfunction "OUT_3") (pintype "power_in"))
      (node (ref "U6") (pin "1") (pinfunction "VDD_1") (pintype "power_in"))
      (node (ref "U7") (pin "4") (pinfunction "C_4") (pintype "passive"))
    )
    (net (code "5") (name "+12") (class "Default")
      (node (ref "C40") (pin "2") (pinfunction "2_2") (pintype "passive"))
      (node (ref "C41") (pin "2") (pinfunction "2_2") (pintype "passive"))
      (node (ref "D11") (pin "2") (pinfunction "K_2") (pintype "passive"))
      (node (ref "D13") (pin "2") (pinfunction "K_2") (pintype "passive"))
      (node (ref "D15") (pin "2") (pinfunction "K_2") (pintype "passive"))
      (node (ref "D18") (pin "2") (pinfunction "K_2") (pintype "passive"))
      (node (ref "D20") (pin "2") (pinfunction "K_2") (pintype "passive"))
      (node (ref "D26") (pin "2") (pinfunction "K_2") (pintype "passive"))
      (node (ref "D42") (pin "2") (pinfunction "K_2") (pintype "passive"))
      (node (ref "K2") (pin "L1") (pinfunction "T1_L1") (pintype "passive"))
      (node (ref "K3") (pin "L1") (pinfunction "T1_L1") (pintype "passive"))
      (node (ref "K4") (pin "L1") (pinfunction "T1_L1") (pintype "passive"))
      (node (ref "K5") (pin "L1") (pinfunction "T1_L1") (pintype "passive"))
      (node (ref "K6") (pin "L1") (pinfunction "T1_L1") (pintype "passive"))
      (node (ref "K7") (pin "L1") (pinfunction "T1_L1") (pintype "passive"))
      (node (ref "K9") (pin "L1") (pinfunction "T1_L1") (pintype "passive"))
      (node (ref "R40") (pin "2") (pinfunction "2_2") (pintype "passive"))
      (node (ref "R48") (pin "2") (pinfunction "2_2") (pintype "passive"))
      (node (ref "R53") (pin "2") (pinfunction "2_2") (pintype "passive"))
      (node (ref "R58") (pin "2") (pinfunction "2_2") (pintype "passive"))
      (node (ref "R59") (pin "2") (pinfunction "2_2") (pintype "passive"))
      (node (ref "R64") (pin "2") (pinfunction "2_2") (pintype "passive"))
      (node (ref "R69") (pin "2") (pinfunction "2_2") (pintype "passive"))
      (node (ref "U19") (pin "3") (pinfunction "OUT_3") (pintype "power_in"))
    )
    (net (code "6") (name "+12_ISOL") (class "Default")
      (node (ref "C30") (pin "2") (pinfunction "2_2") (pintype "passive"))
      (node (ref "C31") (pin "2") (pinfunction "2_2") (pintype "passive"))
      (node (ref "P7") (pin "1") (pinfunction "1_1") (pintype "passive"))
      (node (ref "U13") (pin "3") (pinfunction "OUT_3") (pintype "power_in"))
    )
    (net (code "7") (name "+24_ISOL") (class "Default")
      (node (ref "C34") (pin "2") (pinfunction "2_2") (pintype "passive"))
      (node (ref "C35") (pin "2") (pinfunction "2_2") (pintype "passive"))
      (node (ref "P7") (pin "3") (pinfunction "3_3") (pintype "passive"))
      (node (ref "U16") (pin "3") (pinfunction "OUT_3") (pintype "power_in"))
    )
    (net (code "8") (name "AGND") (class "Default")
      (node (ref "C27") (pin "1") (pinfunction "1_1") (pintype "passive"))
      (node (ref "C28") (pin "1") (pinfunction "1_1") (pintype "passive"))
      (node (ref "C37") (pin "1") (pinfunction "1_1") (pintype "passive"))
      (node (ref "C38") (pin "1") (pinfunction "1_1") (pintype "passive"))
      (node (ref "C39") (pin "2") (pinfunction "2_2") (pintype "passive"))
      (node (ref "C40") (pin "1") (pinfunction "1_1") (pintype "passive"))
      (node (ref "C41") (pin "1") (pinfunction "1_1") (pintype "passive"))
      (node (ref "C42") (pin "1") (pinfunction "1_1") (pintype "passive"))
      (node (ref "C43") (pin "1") (pinfunction "1_1") (pintype "passive"))
      (node (ref "C44") (pin "1") (pinfunction "1_1") (pintype "passive"))
      (node (ref "C45") (pin "2") (pinfunction "2_2") (pintype "passive"))
      (node (ref "C46") (pin "1") (pinfunction "1_1") (pintype "passive"))
      (node (ref "C47") (pin "1") (pinfunction "1_1") (pintype "passive"))
      (node (ref "C48") (pin "1") (pinfunction "1_1") (pintype "passive"))
      (node (ref "C49") (pin "1") (pinfunction "1_1") (pintype "passive"))
      (node (ref "C51") (pin "1") (pinfunction "1_1") (pintype "passive"))
      (node (ref "D38") (pin "1") (pinfunction "A_1") (pintype "passive"))
      (node (ref "D40") (pin "1") (pinfunction "A_1") (pintype "passive"))
      (node (ref "J4") (pin "3") (pinfunction "3_3") (pintype "passive"))
      (node (ref "J5") (pin "4") (pinfunction "GND_4") (pintype "power_in"))
      (node (ref "J5") (pin "5") (pinfunction "SHLD_5") (pintype "passive"))
      (node (ref "J5") (pin "6") (pinfunction "SHLD_6") (pintype "passive"))
      (node (ref "J8") (pin "7") (pinfunction "7_7") (pintype "passive"))
      (node (ref "J9") (pin "1") (pinfunction "1_1") (pintype "passive"))
      (node (ref "LCD1") (pin "1") (pinfunction "VSS_1") (pintype "power_in"))
      (node (ref "LCD1") (pin "15") (pinfunction "A_15") (pintype "power_in"))
      (node (ref "Q2") (pin "E") (pinfunction "E_E") (pintype "passive"))
      (node (ref "Q3") (pin "E") (pinfunction "E_E") (pintype "passive"))
      (node (ref "Q4") (pin "E") (pinfunction "E_E") (pintype "passive"))
      (node (ref "Q5") (pin "E") (pinfunction "E_E") (pintype "passive"))
      (node (ref "Q6") (pin "E") (pinfunction "E_E") (pintype "passive"))
      (node (ref "Q7") (pin "E") (pinfunction "E_E") (pintype "passive"))
      (node (ref "Q9") (pin "E") (pinfunction "E_E") (pintype "passive"))
      (node (ref "R100") (pin "2") (pinfunction "2_2") (pintype "passive"))
      (node (ref "R28") (pin "1") (pinfunction "1_1") (pintype "passive"))
      (node (ref "R51") (pin "2") (pinfunction "2_2") (pintype "passive"))
      (node (ref "R52") (pin "2") (pinfunction "BOT_2") (pintype "passive"))
      (node (ref "S1") (pin "2") (pinfunction "2_2") (pintype "passive"))
      (node (ref "U10") (pin "3") (pinfunction "E_3") (pintype "passive"))
      (node (ref "U12") (pin "3") (pinfunction "E_3") (pintype "passive"))
      (node (ref "U14") (pin "3") (pinfunction "E_3") (pintype "passive"))
      (node (ref "U15") (pin "3") (pinfunction "E_3") (pintype "passive"))
      (node (ref "U17") (pin "3") (pinfunction "E_3") (pintype "passive"))
      (node (ref "U18") (pin "3") (pinfunction "E_3") (pintype "passive"))
      (node (ref "U19") (pin "2") (pinfunction "GND_2") (pintype "power_in"))
      (node (ref "U20") (pin "2") (pinfunction "GND_2") (pintype "power_in"))
      (node (ref "U21") (pin "2") (pinfunction "K_2") (pintype "passive"))
      (node (ref "U7") (pin "2") (pinfunction "K_2") (pintype "passive"))
      (node (ref "U8") (pin "12") (pinfunction "VSS_12") (pintype "power_in"))
      (node (ref "U8") (pin "31") (pinfunction "VSS_31") (pintype "power_in"))
    )
    (net (code "9") (name "COM_RX") (class "Default")
      (node (ref "J4") (pin "4") (pinfunction "4_4") (pintype "passive"))
      (node (ref "R97") (pin "1") (pinfunction "1_1") (pintype "passive"))
      (node (ref "U8") (pin "39") (pinfunction "RB6/PGC_39") (pintype "bidirectional"))
    )
    (net (code "10") (name "COM_TX") (class "Default")
      (node (ref "R51") (pin "1") (pinfunction "1_1") (pintype "passive"))
      (node (ref "U8") (pin "38") (pinfunction "RB5_38") (pintype "bidirectional"))
      (node (ref "U9") (pin "3") (pinfunction "E_3") (pintype "passive"))
    )
    (net (code "11") (name "CTS") (class "Default")
      (node (ref "R7") (pin "2") (pinfunction "2_2") (pintype "passive"))
      (node (ref "U1") (pin "43") (pinfunction "RP4/DPLN/SDA1/CN54/RD9_43") (pintype "bidirectional"))
    )
    (net (code "12") (name "E") (class "Default")
      (node (ref "J9") (pin "6") (pinfunction "6_6") (pintype "passive"))
      (node (ref "LCD1") (pin "6") (pinfunction "E_6") (pintype "input"))
      (node (ref "U8") (pin "37") (pinfunction "RB4_37") (pintype "bidirectional"))
    )
    (net (code "13") (name "GND") (class "Default")
      (node (ref "C1") (pin "1") (pinfunction "1_1") (pintype "passive"))
      (node (ref "C10") (pin "1") (pinfunction "1_1") (pintype "passive"))
      (node (ref "C11") (pin "1") (pinfunction "1_1") (pintype "passive"))
      (node (ref "C12") (pin "1") (pinfunction "1_1") (pintype "passive"))
      (node (ref "C13") (pin "1") (pinfunction "1_1") (pintype "passive"))
      (node (ref "C14") (pin "1") (pinfunction "1_1") (pintype "passive"))
      (node (ref "C15") (pin "1") (pinfunction "1_1") (pintype "passive"))
      (node (ref "C16") (pin "1") (pinfunction "1_1") (pintype "passive"))
      (node (ref "C17") (pin "1") (pinfunction "1_1") (pintype "passive"))
      (node (ref "C18") (pin "1") (pinfunction "1_1") (pintype "passive"))
      (node (ref "C19") (pin "1") (pinfunction "1_1") (pintype "passive"))
      (node (ref "C2") (pin "1") (pinfunction "1_1") (pintype "passive"))
      (node (ref "C3") (pin "1") (pinfunction "1_1") (pintype "passive"))
      (node (ref "C4") (pin "1") (pinfunction "1_1") (pintype "passive"))
      (node (ref "C5") (pin "1") (pinfunction "1_1") (pintype "passive"))
      (node (ref "C6") (pin "1") (pinfunction "1_1") (pintype "passive"))
      (node (ref "C7") (pin "1") (pinfunction "1_1") (pintype "passive"))
      (node (ref "C8") (pin "1") (pinfunction "1_1") (pintype "passive"))
      (node (ref "C9") (pin "1") (pinfunction "1_1") (pintype "passive"))
      (node (ref "D9") (pin "2") (pinfunction "K_2") (pintype "passive"))
      (node (ref "J1") (pin "3") (pinfunction "3_3") (pintype "passive"))
      (node (ref "J2") (pin "1") (pinfunction "1_1") (pintype "passive"))
      (node (ref "J3") (pin "5") (pinfunction "SHLD_5") (pintype "passive"))
      (node (ref "J3") (pin "6") (pinfunction "SHLD_6") (pintype "passive"))
      (node (ref "J3") (pin "7") (pinfunction "SHLD_7") (pintype "passive"))
      (node (ref "J3") (pin "8") (pinfunction "SHLD_8") (pintype "passive"))
      (node (ref "J3") (pin "9") (pinfunction "SHLD_9") (pintype "passive"))
      (node (ref "J7") (pin "1") (pinfunction "1_1") (pintype "passive"))
      (node (ref "R14") (pin "1") (pinfunction "1_1") (pintype "passive"))
      (node (ref "R24") (pin "1") (pinfunction "1_1") (pintype "passive"))
      (node (ref "R25") (pin "1") (pinfunction "1_1") (pintype "passive"))
      (node (ref "R26") (pin "1") (pinfunction "1_1") (pintype "passive"))
      (node (ref "R37") (pin "2") (pinfunction "2_2") (pintype "passive"))
      (node (ref "R8") (pin "1") (pinfunction "1_1") (pintype "passive"))
      (node (ref "RV1") (pin "1") (pinfunction "1_1") (pintype "passive"))
      (node (ref "RV2") (pin "1") (pinfunction "1_1") (pintype "passive"))
      (node (ref "RV3") (pin "1") (pinfunction "1_1") (pintype "passive"))
      (node (ref "RV4") (pin "1") (pinfunction "1_1") (pintype "passive"))
      (node (ref "TFLASH1") (pin "P10") (pinfunction "VSS3_P10") (pintype "passive"))
      (node (ref "TFLASH1") (pin "P11") (pinfunction "VSS4_P11") (pintype "passive"))
      (node (ref "TFLASH1") (pin "P12") (pinfunction "VSS5_P12") (pintype "passive"))
      (node (ref "TFLASH1") (pin "P6") (pinfunction "VSS1_P6") (pintype "passive"))
      (node (ref "TFLASH1") (pin "P9") (pinfunction "VSS2_P9") (pintype "passive"))
      (node (ref "U1") (pin "20") (pinfunction "AVSS_20") (pintype "power_in"))
      (node (ref "U1") (pin "25") (pinfunction "VSS_25") (pintype "power_in"))
      (node (ref "U1") (pin "41") (pinfunction "VSS_41") (pintype "power_in"))
      (node (ref "U1") (pin "9") (pinfunction "VSS_9") (pintype "power_in"))
      (node (ref "U2") (pin "4") (pinfunction "VSS_4") (pintype "power_in"))
      (node (ref "U22") (pin "2") (pinfunction "K_2") (pintype "passive"))
      (node (ref "U3") (pin "1") (pinfunction "GND_1") (pintype "power_in"))
      (node (ref "U3") (pin "10") (pinfunction "GND_10") (pintype "power_in"))
      (node (ref "U3") (pin "18") (pinfunction "GND_18") (pintype "power_in"))
      (node (ref "U3") (pin "19") (pinfunction "GND_19") (pintype "power_in"))
      (node (ref "U3") (pin "25") (pinfunction "GND_25") (pintype "power_in"))
      (node (ref "U3") (pin "28") (pinfunction "GND_28") (pintype "power_in"))
      (node (ref "U3") (pin "30") (pinfunction "GND_30") (pintype "power_in"))
      (node (ref "U3") (pin "36") (pinfunction "GND_36") (pintype "power_in"))
      (node (ref "U4") (pin "1") (pinfunction "GND_1") (pintype "power_in"))
      (node (ref "U5") (pin "1") (pinfunction "ADJ_1") (pintype "input"))
      (node (ref "Y1") (pin "2") (pinfunction "OSC2_2") (pintype "passive"))
      (node (ref "Y1") (pin "4") (pinfunction "OSC4_4") (pintype "passive"))
    )
    (net (code "14") (name "IN-DIG_1") (class "Default")
      (node (ref "C27") (pin "2") (pinfunction "2_2") (pintype "passive"))
      (node (ref "R74") (pin "2") (pinfunction "2_2") (pintype "passive"))
      (node (ref "U8") (pin "2") (pinfunction "RA0/AN0_2") (pintype "bidirectional"))
    )
    (net (code "15") (name "IN-DIG_2") (class "Default")
      (node (ref "C28") (pin "2") (pinfunction "2_2") (pintype "passive"))
      (node (ref "R75") (pin "2") (pinfunction "2_2") (pintype "passive"))
      (node (ref "U8") (pin "3") (pinfunction "RA1/AN1_3") (pintype "bidirectional"))
    )
    (net (code "16") (name "IN-DIG_3") (class "Default")
      (node (ref "C37") (pin "2") (pinfunction "2_2") (pintype "passive"))
      (node (ref "R84") (pin "2") (pinfunction "2_2") (pintype "passive"))
      (node (ref "U8") (pin "4") (pinfunction "RA2/AN2_4") (pintype "bidirectional"))
    )
    (net (code "17") (name "IN-DIG_4") (class "Default")
      (node (ref "C38") (pin "2") (pinfunction "2_2") (pintype "passive"))
      (node (ref "R86") (pin "2") (pinfunction "2_2") (pintype "passive"))
      (node (ref "U8") (pin "5") (pinfunction "RA3/AN3/VREF_5") (pintype "bidirectional"))
    )
    (net (code "18") (name "IN-DIG_5") (class "Default")
      (node (ref "C43") (pin "2") (pinfunction "2_2") (pintype "passive"))
      (node (ref "R92") (pin "2") (pinfunction "2_2") (pintype "passive"))
      (node (ref "U8") (pin "6") (pinfunction "RA4/T0CKI_6") (pintype "bidirectional"))
    )
    (net (code "19") (name "IN-DIG_6") (class "Default")
      (node (ref "C44") (pin "2") (pinfunction "2_2") (pintype "passive"))
      (node (ref "R94") (pin "2") (pinfunction "2_2") (pintype "passive"))
      (node (ref "U8") (pin "7") (pinfunction "RA5/AN4/~{SS}_7") (pintype "bidirectional"))
    )
    (net (code "20") (name "LED0") (class "Default")
      (node (ref "R15") (pin "1") (pinfunction "1_1") (pintype "passive"))
      (node (ref "U1") (pin "44") (pinfunction "RP3/SCL1/PMCS2/CN55/RD10_44") (pintype "bidirectional"))
    )
    (net (code "21") (name "LED1") (class "Default")
      (node (ref "R19") (pin "1") (pinfunction "1_1") (pintype "passive"))
      (node (ref "U1") (pin "45") (pinfunction "RP12/PMCS1/CN56/RD11_45") (pintype "bidirectional"))
    )
    (net (code "22") (name "LED2") (class "Default")
      (node (ref "R20") (pin "1") (pinfunction "1_1") (pintype "passive"))
      (node (ref "U1") (pin "46") (pinfunction "RP11/DMH/CN49/INT0/RD0_46") (pintype "bidirectional"))
    )
    (net (code "23") (name "LED3") (class "Default")
      (node (ref "R21") (pin "1") (pinfunction "1_1") (pintype "passive"))
      (node (ref "U1") (pin "47") (pinfunction "SOSCI/C3IND/CN1/RC13_47") (pintype "bidirectional"))
    )
    (net (code "24") (name "LED4") (class "Default")
      (node (ref "R22") (pin "1") (pinfunction "1_1") (pintype "passive"))
      (node (ref "U1") (pin "48") (pinfunction "RPI37/SOSCO/C3INC/TICK/CN0/RC14_48") (pintype "bidirectional"))
    )
    (net (code "25") (name "MCLR") (class "Default")
      (node (ref "J1") (pin "1") (pinfunction "1_1") (pintype "passive"))
      (node (ref "R2") (pin "1") (pinfunction "1_1") (pintype "passive"))
      (node (ref "U1") (pin "7") (pinfunction "~{MCLR}_7") (pintype "input"))
    )
    (net (code "26") (name "MCLR3") (class "Default")
      (node (ref "J6") (pin "1") (pinfunction "1_1") (pintype "passive"))
      (node (ref "R101") (pin "2") (pinfunction "2_2") (pintype "passive"))
      (node (ref "U6") (pin "4") (pinfunction "RA3/~{MCLR}/VPP_4") (pintype "bidirectional"))
    )
    (net (code "27") (name "MCLR_2") (class "Default")
      (node (ref "J4") (pin "1") (pinfunction "1_1") (pintype "passive"))
      (node (ref "R45") (pin "1") (pinfunction "1_1") (pintype "passive"))
      (node (ref "U8") (pin "1") (pinfunction "~{MCLR}/VPP_1") (pintype "input"))
    )
    (net (code "28") (name "Net-(C11-Pad2)") (class "Default")
      (node (ref "C11") (pin "2") (pinfunction "2_2") (pintype "passive"))
      (node (ref "R1") (pin "1") (pinfunction "1_1") (pintype "passive"))
      (node (ref "R2") (pin "2") (pinfunction "2_2") (pintype "passive"))
    )
    (net (code "29") (name "Net-(D2-K)") (class "Default")
      (node (ref "D2") (pin "2") (pinfunction "K_2") (pintype "passive"))
      (node (ref "R15") (pin "2") (pinfunction "2_2") (pintype "passive"))
    )
    (net (code "30") (name "Net-(D3-K)") (class "Default")
      (node (ref "D3") (pin "2") (pinfunction "K_2") (pintype "passive"))
      (node (ref "R19") (pin "2") (pinfunction "2_2") (pintype "passive"))
    )
    (net (code "31") (name "Net-(D4-K)") (class "Default")
      (node (ref "D4") (pin "2") (pinfunction "K_2") (pintype "passive"))
      (node (ref "R20") (pin "2") (pinfunction "2_2") (pintype "passive"))
    )
    (net (code "32") (name "Net-(D5-K)") (class "Default")
      (node (ref "D5") (pin "2") (pinfunction "K_2") (pintype "passive"))
      (node (ref "R21") (pin "2") (pinfunction "2_2") (pintype "passive"))
    )
    (net (code "33") (name "Net-(D6-K)") (class "Default")
      (node (ref "D6") (pin "2") (pinfunction "K_2") (pintype "passive"))
      (node (ref "R22") (pin "2") (pinfunction "2_2") (pintype "passive"))
    )
    (net (code "34") (name "Net-(D9-A)") (class "Default")
      (node (ref "D9") (pin "1") (pinfunction "A_1") (pintype "passive"))
      (node (ref "R27") (pin "1") (pinfunction "1_1") (pintype "passive"))
    )
    (net (code "35") (name "Net-(D10-A)") (class "Default")
      (node (ref "D10") (pin "1") (pinfunction "A_1") (pintype "passive"))
      (node (ref "R40") (pin "1") (pinfunction "1_1") (pintype "passive"))
    )
    (net (code "36") (name "Net-(D10-K)") (class "Default")
      (node (ref "D10") (pin "2") (pinfunction "K_2") (pintype "passive"))
      (node (ref "D11") (pin "1") (pinfunction "A_1") (pintype "passive"))
      (node (ref "K2") (pin "L2") (pinfunction "T2_L2") (pintype "passive"))
      (node (ref "Q2") (pin "C") (pinfunction "C_C") (pintype "passive"))
    )
    (net (code "37") (name "Net-(D12-A)") (class "Default")
      (node (ref "D12") (pin "1") (pinfunction "A_1") (pintype "passive"))
      (node (ref "R48") (pin "1") (pinfunction "1_1") (pintype "passive"))
    )
    (net (code "38") (name "Net-(D12-K)") (class "Default")
      (node (ref "D12") (pin "2") (pinfunction "K_2") (pintype "passive"))
      (node (ref "D13") (pin "1") (pinfunction "A_1") (pintype "passive"))
      (node (ref "K3") (pin "L2") (pinfunction "T2_L2") (pintype "passive"))
      (node (ref "Q3") (pin "C") (pinfunction "C_C") (pintype "passive"))
    )
    (net (code "39") (name "Net-(D14-A)") (class "Default")
      (node (ref "D14") (pin "1") (pinfunction "A_1") (pintype "passive"))
      (node (ref "R53") (pin "1") (pinfunction "1_1") (pintype "passive"))
    )
    (net (code "40") (name "Net-(D14-K)") (class "Default")
      (node (ref "D14") (pin "2") (pinfunction "K_2") (pintype "passive"))
      (node (ref "D15") (pin "1") (pinfunction "A_1") (pintype "passive"))
      (node (ref "K4") (pin "L2") (pinfunction "T2_L2") (pintype "passive"))
      (node (ref "Q4") (pin "C") (pinfunction "C_C") (pintype "passive"))
    )
    (net (code "41") (name "Net-(D16-K)") (class "Default")
      (node (ref "D16") (pin "2") (pinfunction "K_2") (pintype "passive"))
      (node (ref "R65") (pin "2") (pinfunction "2_2") (pintype "passive"))
    )
    (net (code "42") (name "Net-(D17-A)") (class "Default")
      (node (ref "D17") (pin "1") (pinfunction "A_1") (pintype "passive"))
      (node (ref "R58") (pin "1") (pinfunction "1_1") (pintype "passive"))
    )
    (net (code "43") (name "Net-(D17-K)") (class "Default")
      (node (ref "D17") (pin "2") (pinfunction "K_2") (pintype "passive"))
      (node (ref "D18") (pin "1") (pinfunction "A_1") (pintype "passive"))
      (node (ref "K5") (pin "L2") (pinfunction "T2_L2") (pintype "passive"))
      (node (ref "Q5") (pin "C") (pinfunction "C_C") (pintype "passive"))
    )
    (net (code "44") (name "Net-(D19-A)") (class "Default")
      (node (ref "D19") (pin "1") (pinfunction "A_1") (pintype "passive"))
      (node (ref "R59") (pin "1") (pinfunction "1_1") (pintype "passive"))
    )
    (net (code "45") (name "Net-(D19-K)") (class "Default")
      (node (ref "D19") (pin "2") (pinfunction "K_2") (pintype "passive"))
      (node (ref "D20") (pin "1") (pinfunction "A_1") (pintype "passive"))
      (node (ref "K6") (pin "L2") (pinfunction "T2_L2") (pintype "passive"))
      (node (ref "Q6") (pin "C") (pinfunction "C_C") (pintype "passive"))
    )
    (net (code "46") (name "Net-(D21-A)") (class "Default")
      (node (ref "D21") (pin "1") (pinfunction "A_1") (pintype "passive"))
      (node (ref "D23") (pin "2") (pinfunction "K_2") (pintype "passive"))
      (node (ref "P8") (pin "1") (pinfunction "1_1") (pintype "passive"))
      (node (ref "R72") (pin "1") (pinfunction "1_1") (pintype "passive"))
    )
    (net (code "47") (name "Net-(D21-K)") (class "Default")
      (node (ref "D21") (pin "2") (pinfunction "K_2") (pintype "passive"))
      (node (ref "R76") (pin "2") (pinfunction "2_2") (pintype "passive"))
    )
    (net (code "48") (name "Net-(D22-A)") (class "Default")
      (node (ref "D22") (pin "1") (pinfunction "A_1") (pintype "passive"))
      (node (ref "D24") (pin "2") (pinfunction "K_2") (pintype "passive"))
      (node (ref "P8") (pin "2") (pinfunction "2_2") (pintype "passive"))
      (node (ref "R73") (pin "1") (pinfunction "1_1") (pintype "passive"))
    )
    (net (code "49") (name "Net-(D22-K)") (class "Default")
      (node (ref "D22") (pin "2") (pinfunction "K_2") (pintype "passive"))
      (node (ref "R77") (pin "2") (pinfunction "2_2") (pintype "passive"))
    )
    (net (code "50") (name "Net-(D25-A)") (class "Default")
      (node (ref "D25") (pin "1") (pinfunction "A_1") (pintype "passive"))
      (node (ref "R64") (pin "1") (pinfunction "1_1") (pintype "passive"))
    )
    (net (code "51") (name "Net-(D25-K)") (class "Default")
      (node (ref "D25") (pin "2") (pinfunction "K_2") (pintype "passive"))
      (node (ref "D26") (pin "1") (pinfunction "A_1") (pintype "passive"))
      (node (ref "K7") (pin "L2") (pinfunction "T2_L2") (pintype "passive"))
      (node (ref "Q7") (pin "C") (pinfunction "C_C") (pintype "passive"))
    )
    (net (code "52") (name "Net-(D33-A)") (class "Default")
      (node (ref "D33") (pin "1") (pinfunction "A_1") (pintype "passive"))
      (node (ref "D35") (pin "2") (pinfunction "K_2") (pintype "passive"))
      (node (ref "P11") (pin "1") (pinfunction "1_1") (pintype "passive"))
      (node (ref "R83") (pin "1") (pinfunction "1_1") (pintype "passive"))
    )
    (net (code "53") (name "Net-(D33-K)") (class "Default")
      (node (ref "D33") (pin "2") (pinfunction "K_2") (pintype "passive"))
      (node (ref "R87") (pin "2") (pinfunction "2_2") (pintype "passive"))
    )
    (net (code "54") (name "Net-(D34-A)") (class "Default")
      (node (ref "D34") (pin "1") (pinfunction "A_1") (pintype "passive"))
      (node (ref "D36") (pin "2") (pinfunction "K_2") (pintype "passive"))
      (node (ref "P11") (pin "2") (pinfunction "2_2") (pintype "passive"))
      (node (ref "R85") (pin "1") (pinfunction "1_1") (pintype "passive"))
    )
    (net (code "55") (name "Net-(D34-K)") (class "Default")
      (node (ref "D34") (pin "2") (pinfunction "K_2") (pintype "passive"))
      (node (ref "R88") (pin "2") (pinfunction "2_2") (pintype "passive"))
    )
    (net (code "56") (name "Net-(D37-K)") (class "Default")
      (node (ref "C39") (pin "1") (pinfunction "1_1") (pintype "passive"))
      (node (ref "C42") (pin "2") (pinfunction "2_2") (pintype "passive"))
      (node (ref "C45") (pin "1") (pinfunction "1_1") (pintype "passive"))
      (node (ref "C48") (pin "2") (pinfunction "2_2") (pintype "passive"))
      (node (ref "D37") (pin "2") (pinfunction "K_2") (pintype "passive"))
      (node (ref "D39") (pin "2") (pinfunction "K_2") (pintype "passive"))
      (node (ref "U19") (pin "1") (pinfunction "IN_1") (pintype "power_in"))
      (node (ref "U20") (pin "1") (pinfunction "IN_1") (pintype "power_in"))
    )
    (net (code "57") (name "Net-(D41-A)") (class "Default")
      (node (ref "D41") (pin "1") (pinfunction "A_1") (pintype "passive"))
      (node (ref "R69") (pin "1") (pinfunction "1_1") (pintype "passive"))
    )
    (net (code "58") (name "Net-(D41-K)") (class "Default")
      (node (ref "D41") (pin "2") (pinfunction "K_2") (pintype "passive"))
      (node (ref "D42") (pin "1") (pinfunction "A_1") (pintype "passive"))
      (node (ref "K9") (pin "L2") (pinfunction "T2_L2") (pintype "passive"))
      (node (ref "Q9") (pin "C") (pinfunction "C_C") (pintype "passive"))
    )
    (net (code "59") (name "Net-(D45-A)") (class "Default")
      (node (ref "D45") (pin "1") (pinfunction "A_1") (pintype "passive"))
      (node (ref "D47") (pin "2") (pinfunction "K_2") (pintype "passive"))
      (node (ref "P12") (pin "1") (pinfunction "1_1") (pintype "passive"))
      (node (ref "R91") (pin "1") (pinfunction "1_1") (pintype "passive"))
    )
    (net (code "60") (name "Net-(D45-K)") (class "Default")
      (node (ref "D45") (pin "2") (pinfunction "K_2") (pintype "passive"))
      (node (ref "R95") (pin "2") (pinfunction "2_2") (pintype "passive"))
    )
    (net (code "61") (name "Net-(D46-A)") (class "Default")
      (node (ref "D46") (pin "1") (pinfunction "A_1") (pintype "passive"))
      (node (ref "D48") (pin "2") (pinfunction "K_2") (pintype "passive"))
      (node (ref "P12") (pin "2") (pinfunction "2_2") (pintype "passive"))
      (node (ref "R93") (pin "1") (pinfunction "1_1") (pintype "passive"))
    )
    (net (code "62") (name "Net-(D46-K)") (class "Default")
      (node (ref "D46") (pin "2") (pinfunction "K_2") (pintype "passive"))
      (node (ref "R96") (pin "2") (pinfunction "2_2") (pintype "passive"))
    )
    (net (code "63") (name "Net-(J2-Pad2)") (class "Default")
      (node (ref "J2") (pin "2") (pinfunction "2_2") (pintype "passive"))
      (node (ref "R4") (pin "1") (pinfunction "1_1") (pintype "passive"))
    )
    (net (code "64") (name "Net-(J2-Pad4)") (class "Default")
      (node (ref "J2") (pin "4") (pinfunction "4_4") (pintype "passive"))
      (node (ref "R5") (pin "1") (pinfunction "1_1") (pintype "passive"))
    )
    (net (code "65") (name "Net-(J2-Pad5)") (class "Default")
      (node (ref "J2") (pin "5") (pinfunction "5_5") (pintype "passive"))
      (node (ref "R6") (pin "1") (pinfunction "1_1") (pintype "passive"))
    )
    (net (code "66") (name "Net-(J2-Pad6)") (class "Default")
      (node (ref "J2") (pin "6") (pinfunction "6_6") (pintype "passive"))
      (node (ref "R7") (pin "1") (pinfunction "1_1") (pintype "passive"))
    )
    (net (code "67") (name "Net-(K2-COM)") (class "Default")
      (node (ref "K2") (pin "C") (pinfunction "COM_C") (pintype "passive"))
      (node (ref "P3") (pin "2") (pinfunction "2_2") (pintype "passive"))
    )
    (net (code "68") (name "Net-(K2-NC)") (class "Default")
      (node (ref "K2") (pin "NF") (pinfunction "NC_NF") (pintype "passive"))
      (node (ref "P3") (pin "1") (pinfunction "1_1") (pintype "passive"))
    )
    (net (code "69") (name "Net-(K2-NO)") (class "Default")
      (node (ref "K2") (pin "NA") (pinfunction "NO_NA") (pintype "passive"))
      (node (ref "P3") (pin "3") (pinfunction "3_3") (pintype "passive"))
    )
    (net (code "70") (name "Net-(K3-COM)") (class "Default")
      (node (ref "K3") (pin "C") (pinfunction "COM_C") (pintype "passive"))
      (node (ref "P5") (pin "2") (pinfunction "2_2") (pintype "passive"))
    )
    (net (code "71") (name "Net-(K3-NC)") (class "Default")
      (node (ref "K3") (pin "NF") (pinfunction "NC_NF") (pintype "passive"))
      (node (ref "P5") (pin "1") (pinfunction "1_1") (pintype "passive"))
    )
    (net (code "72") (name "Net-(K3-NO)") (class "Default")
      (node (ref "K3") (pin "NA") (pinfunction "NO_NA") (pintype "passive"))
      (node (ref "P5") (pin "3") (pinfunction "3_3") (pintype "passive"))
    )
    (net (code "73") (name "Net-(K4-COM)") (class "Default")
      (node (ref "K4") (pin "C") (pinfunction "COM_C") (pintype "passive"))
      (node (ref "P6") (pin "2") (pinfunction "2_2") (pintype "passive"))
    )
    (net (code "74") (name "Net-(K4-NC)") (class "Default")
      (node (ref "K4") (pin "NF") (pinfunction "NC_NF") (pintype "passive"))
      (node (ref "P6") (pin "1") (pinfunction "1_1") (pintype "passive"))
    )
    (net (code "75") (name "Net-(K4-NO)") (class "Default")
      (node (ref "K4") (pin "NA") (pinfunction "NO_NA") (pintype "passive"))
      (node (ref "P6") (pin "3") (pinfunction "3_3") (pintype "passive"))
    )
    (net (code "76") (name "Net-(K5-COM)") (class "Default")
      (node (ref "K5") (pin "C") (pinfunction "COM_C") (pintype "passive"))
      (node (ref "P9") (pin "2") (pinfunction "2_2") (pintype "passive"))
    )
    (net (code "77") (name "Net-(K5-NC)") (class "Default")
      (node (ref "K5") (pin "NF") (pinfunction "NC_NF") (pintype "passive"))
      (node (ref "P9") (pin "1") (pinfunction "1_1") (pintype "passive"))
    )
    (net (code "78") (name "Net-(K5-NO)") (class "Default")
      (node (ref "K5") (pin "NA") (pinfunction "NO_NA") (pintype "passive"))
      (node (ref "P9") (pin "3") (pinfunction "3_3") (pintype "passive"))
    )
    (net (code "79") (name "Net-(K6-COM)") (class "Default")
      (node (ref "K6") (pin "C") (pinfunction "COM_C") (pintype "passive"))
      (node (ref "P10") (pin "2") (pinfunction "2_2") (pintype "passive"))
    )
    (net (code "80") (name "Net-(K6-NC)") (class "Default")
      (node (ref "K6") (pin "NF") (pinfunction "NC_NF") (pintype "passive"))
      (node (ref "P10") (pin "1") (pinfunction "1_1") (pintype "passive"))
    )
    (net (code "81") (name "Net-(K6-NO)") (class "Default")
      (node (ref "K6") (pin "NA") (pinfunction "NO_NA") (pintype "passive"))
      (node (ref "P10") (pin "3") (pinfunction "3_3") (pintype "passive"))
    )
    (net (code "82") (name "Net-(K7-COM)") (class "Default")
      (node (ref "K7") (pin "C") (pinfunction "COM_C") (pintype "passive"))
      (node (ref "P13") (pin "2") (pinfunction "2_2") (pintype "passive"))
    )
    (net (code "83") (name "Net-(K7-NC)") (class "Default")
      (node (ref "K7") (pin "NF") (pinfunction "NC_NF") (pintype "passive"))
      (node (ref "P13") (pin "1") (pinfunction "1_1") (pintype "passive"))
    )
    (net (code "84") (name "Net-(K7-NO)") (class "Default")
      (node (ref "K7") (pin "NA") (pinfunction "NO_NA") (pintype "passive"))
      (node (ref "P13") (pin "3") (pinfunction "3_3") (pintype "passive"))
    )
    (net (code "85") (name "Net-(K9-COM)") (class "Default")
      (node (ref "K9") (pin "C") (pinfunction "COM_C") (pintype "passive"))
      (node (ref "P15") (pin "2") (pinfunction "2_2") (pintype "passive"))
    )
    (net (code "86") (name "Net-(K9-NC)") (class "Default")
      (node (ref "K9") (pin "NF") (pinfunction "NC_NF") (pintype "passive"))
      (node (ref "P15") (pin "1") (pinfunction "1_1") (pintype "passive"))
    )
    (net (code "87") (name "Net-(K9-NO)") (class "Default")
      (node (ref "K9") (pin "NA") (pinfunction "NO_NA") (pintype "passive"))
      (node (ref "P15") (pin "3") (pinfunction "3_3") (pintype "passive"))
    )
    (net (code "88") (name "Net-(P1-Pad1)") (class "Default")
      (node (ref "P1") (pin "1") (pinfunction "1_1") (pintype "passive"))
      (node (ref "R38") (pin "1") (pinfunction "1_1") (pintype "passive"))
    )
    (net (code "89") (name "Net-(P1-Pad2)") (class "Default")
      (node (ref "P1") (pin "2") (pinfunction "2_2") (pintype "passive"))
      (node (ref "R46") (pin "1") (pinfunction "1_1") (pintype "passive"))
    )
    (net (code "90") (name "Net-(P4-Pad1)") (class "Default")
      (node (ref "P4") (pin "1") (pinfunction "1_1") (pintype "passive"))
      (node (ref "R55") (pin "1") (pinfunction "1_1") (pintype "passive"))
    )
    (net (code "91") (name "Net-(P4-Pad2)") (class "Default")
      (node (ref "P4") (pin "2") (pinfunction "2_2") (pintype "passive"))
      (node (ref "R61") (pin "1") (pinfunction "1_1") (pintype "passive"))
    )
    (net (code "92") (name "Net-(Q2-PadB)") (class "Default")
      (node (ref "Q2") (pin "B") (pinfunction "B_B") (pintype "passive"))
      (node (ref "R47") (pin "2") (pinfunction "2_2") (pintype "passive"))
    )
    (net (code "93") (name "Net-(Q3-PadB)") (class "Default")
      (node (ref "Q3") (pin "B") (pinfunction "B_B") (pintype "passive"))
      (node (ref "R54") (pin "2") (pinfunction "2_2") (pintype "passive"))
    )
    (net (code "94") (name "Net-(Q4-PadB)") (class "Default")
      (node (ref "Q4") (pin "B") (pinfunction "B_B") (pintype "passive"))
      (node (ref "R56") (pin "2") (pinfunction "2_2") (pintype "passive"))
    )
    (net (code "95") (name "Net-(Q5-PadB)") (class "Default")
      (node (ref "Q5") (pin "B") (pinfunction "B_B") (pintype "passive"))
      (node (ref "R60") (pin "2") (pinfunction "2_2") (pintype "passive"))
    )
    (net (code "96") (name "Net-(Q6-PadB)") (class "Default")
      (node (ref "Q6") (pin "B") (pinfunction "B_B") (pintype "passive"))
      (node (ref "R62") (pin "2") (pinfunction "2_2") (pintype "passive"))
    )
    (net (code "97") (name "Net-(Q7-PadB)") (class "Default")
      (node (ref "Q7") (pin "B") (pinfunction "B_B") (pintype "passive"))
      (node (ref "R67") (pin "2") (pinfunction "2_2") (pintype "passive"))
    )
    (net (code "98") (name "Net-(Q9-PadB)") (class "Default")
      (node (ref "Q9") (pin "B") (pinfunction "B_B") (pintype "passive"))
      (node (ref "R79") (pin "2") (pinfunction "2_2") (pintype "passive"))
    )
    (net (code "99") (name "Net-(R11-Pad2)") (class "Default")
      (node (ref "R11") (pin "2") (pinfunction "2_2") (pintype "passive"))
      (node (ref "TFLASH1") (pin "P8") (pinfunction "RSV_P8") (pintype "passive"))
    )
    (net (code "100") (name "Net-(R12-Pad2)") (class "Default")
      (node (ref "R12") (pin "2") (pinfunction "2_2") (pintype "passive"))
      (node (ref "TFLASH1") (pin "P1") (pinfunction "RSV_P1") (pintype "passive"))
    )
    (net (code "101") (name "Net-(U1-VPIO{slash}C2INA{slash}AN3{slash}CN5{slash}RB3)") (class "Default")
      (node (ref "R3") (pin "1") (pinfunction "1_1") (pintype "passive"))
      (node (ref "R8") (pin "2") (pinfunction "2_2") (pintype "passive"))
      (node (ref "U1") (pin "13") (pinfunction "VPIO/C2INA/AN3/CN5/RB3_13") (pintype "bidirectional"))
    )
    (net (code "102") (name "Net-(U3-JTAG_EN)") (class "Default")
      (node (ref "R26") (pin "2") (pinfunction "2_2") (pintype "passive"))
      (node (ref "U3") (pin "21") (pinfunction "JTAG_EN_21") (pintype "input"))
    )
    (net (code "103") (name "Net-(U3-JTAG_RST)") (class "Default")
      (node (ref "R24") (pin "2") (pinfunction "2_2") (pintype "passive"))
      (node (ref "U3") (pin "9") (pinfunction "JTAG_RST_9") (pintype "input"))
    )
    (net (code "104") (name "Net-(U3-JTAG_TKC)") (class "Default")
      (node (ref "R17") (pin "1") (pinfunction "1_1") (pintype "passive"))
      (node (ref "U3") (pin "4") (pinfunction "JTAG_TKC_4") (pintype "input"))
    )
    (net (code "105") (name "Net-(U3-WP)") (class "Default")
      (node (ref "R23") (pin "1") (pinfunction "1_1") (pintype "passive"))
      (node (ref "U3") (pin "16") (pinfunction "WP_16") (pintype "bidirectional"))
    )
    (net (code "106") (name "Net-(U6-RA2{slash}AN2{slash}COUT{slash}T0CKI{slash}INT)") (class "Default")
      (node (ref "C20") (pin "2") (pinfunction "2_2") (pintype "passive"))
      (node (ref "R46") (pin "2") (pinfunction "2_2") (pintype "passive"))
      (node (ref "R49") (pin "2") (pinfunction "2_2") (pintype "passive"))
      (node (ref "U6") (pin "11") (pinfunction "RA2/AN2/COUT/T0CKI/INT_11") (pintype "bidirectional"))
    )
    (net (code "107") (name "Net-(U6-RC0{slash}AN4)") (class "Default")
      (node (ref "C50") (pin "2") (pinfunction "2_2") (pintype "passive"))
      (node (ref "R38") (pin "2") (pinfunction "2_2") (pintype "passive"))
      (node (ref "R42") (pin "2") (pinfunction "2_2") (pintype "passive"))
      (node (ref "U6") (pin "10") (pinfunction "RC0/AN4_10") (pintype "bidirectional"))
    )
    (net (code "108") (name "Net-(U6-RC1{slash}AN5)") (class "Default")
      (node (ref "C22") (pin "2") (pinfunction "2_2") (pintype "passive"))
      (node (ref "R61") (pin "2") (pinfunction "2_2") (pintype "passive"))
      (node (ref "R63") (pin "1") (pinfunction "1_1") (pintype "passive"))
      (node (ref "U6") (pin "9") (pinfunction "RC1/AN5_9") (pintype "bidirectional"))
    )
    (net (code "109") (name "Net-(U6-RC2{slash}AN6)") (class "Default")
      (node (ref "C21") (pin "2") (pinfunction "2_2") (pintype "passive"))
      (node (ref "R55") (pin "2") (pinfunction "2_2") (pintype "passive"))
      (node (ref "R57") (pin "1") (pinfunction "1_1") (pintype "passive"))
      (node (ref "U6") (pin "8") (pinfunction "RC2/AN6_8") (pintype "bidirectional"))
    )
    (net (code "110") (name "Net-(U7-A)") (class "Default")
      (node (ref "R97") (pin "2") (pinfunction "2_2") (pintype "passive"))
      (node (ref "U7") (pin "1") (pinfunction "A_1") (pintype "passive"))
    )
    (net (code "111") (name "Net-(U7-E)") (class "Default")
      (node (ref "R43") (pin "2") (pinfunction "2_2") (pintype "passive"))
      (node (ref "R98") (pin "1") (pinfunction "1_1") (pintype "passive"))
      (node (ref "U7") (pin "3") (pinfunction "E_3") (pintype "passive"))
    )
    (net (code "112") (name "Net-(U8-RC0{slash}T1OSO{slash}T1CKI)") (class "Default")
      (node (ref "R65") (pin "1") (pinfunction "1_1") (pintype "passive"))
      (node (ref "U8") (pin "15") (pinfunction "RC0/T1OSO/T1CKI_15") (pintype "bidirectional"))
    )
    (net (code "113") (name "Net-(U8-RC1{slash}T1OSI{slash}CCP2)") (class "Default")
      (node (ref "S1") (pin "1") (pinfunction "1_1") (pintype "passive"))
      (node (ref "U8") (pin "16") (pinfunction "RC1/T1OSI/CCP2_16") (pintype "bidirectional"))
    )
    (net (code "114") (name "Net-(U8-RC6{slash}TX{slash}CK)") (class "Default")
      (node (ref "R102") (pin "2") (pinfunction "2_2") (pintype "passive"))
      (node (ref "U8") (pin "25") (pinfunction "RC6/TX/CK_25") (pintype "bidirectional"))
    )
    (net (code "115") (name "Net-(U9-A)") (class "Default")
      (node (ref "R50") (pin "1") (pinfunction "1_1") (pintype "passive"))
      (node (ref "U9") (pin "1") (pinfunction "A_1") (pintype "passive"))
    )
    (net (code "116") (name "Net-(U10-A)") (class "Default")
      (node (ref "R72") (pin "2") (pinfunction "2_2") (pintype "passive"))
      (node (ref "U10") (pin "1") (pinfunction "A_1") (pintype "passive"))
    )
    (net (code "117") (name "Net-(U10-C)") (class "Default")
      (node (ref "R70") (pin "1") (pinfunction "1_1") (pintype "passive"))
      (node (ref "R74") (pin "1") (pinfunction "1_1") (pintype "passive"))
      (node (ref "U10") (pin "4") (pinfunction "C_4") (pintype "passive"))
    )
    (net (code "118") (name "Net-(U12-A)") (class "Default")
      (node (ref "R73") (pin "2") (pinfunction "2_2") (pintype "passive"))
      (node (ref "U12") (pin "1") (pinfunction "A_1") (pintype "passive"))
    )
    (net (code "119") (name "Net-(U12-C)") (class "Default")
      (node (ref "R71") (pin "1") (pinfunction "1_1") (pintype "passive"))
      (node (ref "R75") (pin "1") (pinfunction "1_1") (pintype "passive"))
      (node (ref "U12") (pin "4") (pinfunction "C_4") (pintype "passive"))
    )
    (net (code "120") (name "Net-(U14-A)") (class "Default")
      (node (ref "R83") (pin "2") (pinfunction "2_2") (pintype "passive"))
      (node (ref "U14") (pin "1") (pinfunction "A_1") (pintype "passive"))
    )
    (net (code "121") (name "Net-(U14-C)") (class "Default")
      (node (ref "R80") (pin "1") (pinfunction "1_1") (pintype "passive"))
      (node (ref "R84") (pin "1") (pinfunction "1_1") (pintype "passive"))
      (node (ref "U14") (pin "4") (pinfunction "C_4") (pintype "passive"))
    )
    (net (code "122") (name "Net-(U15-A)") (class "Default")
      (node (ref "R85") (pin "2") (pinfunction "2_2") (pintype "passive"))
      (node (ref "U15") (pin "1") (pinfunction "A_1") (pintype "passive"))
    )
    (net (code "123") (name "Net-(U15-C)") (class "Default")
      (node (ref "R81") (pin "1") (pinfunction "1_1") (pintype "passive"))
      (node (ref "R86") (pin "1") (pinfunction "1_1") (pintype "passive"))
      (node (ref "U15") (pin "4") (pinfunction "C_4") (pintype "passive"))
    )
    (net (code "124") (name "Net-(U17-A)") (class "Default")
      (node (ref "R91") (pin "2") (pinfunction "2_2") (pintype "passive"))
      (node (ref "U17") (pin "1") (pinfunction "A_1") (pintype "passive"))
    )
    (net (code "125") (name "Net-(U17-C)") (class "Default")
      (node (ref "R89") (pin "1") (pinfunction "1_1") (pintype "passive"))
      (node (ref "R92") (pin "1") (pinfunction "1_1") (pintype "passive"))
      (node (ref "U17") (pin "4") (pinfunction "C_4") (pintype "passive"))
    )
    (net (code "126") (name "Net-(U18-A)") (class "Default")
      (node (ref "R93") (pin "2") (pinfunction "2_2") (pintype "passive"))
      (node (ref "U18") (pin "1") (pinfunction "A_1") (pintype "passive"))
    )
    (net (code "127") (name "Net-(U18-C)") (class "Default")
      (node (ref "R90") (pin "1") (pinfunction "1_1") (pintype "passive"))
      (node (ref "R94") (pin "1") (pinfunction "1_1") (pintype "passive"))
      (node (ref "U18") (pin "4") (pinfunction "C_4") (pintype "passive"))
    )
    (net (code "128") (name "Net-(U21-A)") (class "Default")
      (node (ref "R102") (pin "1") (pinfunction "1_1") (pintype "passive"))
      (node (ref "U21") (pin "1") (pinfunction "A_1") (pintype "passive"))
    )
    (net (code "129") (name "Net-(U21-E)") (class "Default")
      (node (ref "R36") (pin "2") (pinfunction "2_2") (pintype "passive"))
      (node (ref "R37") (pin "1") (pinfunction "1_1") (pintype "passive"))
      (node (ref "U21") (pin "3") (pinfunction "E_3") (pintype "passive"))
    )
    (net (code "130") (name "Net-(U22-A)") (class "Default")
      (node (ref "R99") (pin "1") (pinfunction "1_1") (pintype "passive"))
      (node (ref "U22") (pin "1") (pinfunction "A_1") (pintype "passive"))
    )
    (net (code "131") (name "Net-(U22-E)") (class "Default")
      (node (ref "R100") (pin "1") (pinfunction "1_1") (pintype "passive"))
      (node (ref "U22") (pin "3") (pinfunction "E_3") (pintype "passive"))
      (node (ref "U8") (pin "26") (pinfunction "RC7/RX/DT_26") (pintype "bidirectional"))
    )
    (net (code "132") (name "OSC1") (class "Default")
      (node (ref "C1") (pin "2") (pinfunction "2_2") (pintype "passive"))
      (node (ref "U1") (pin "39") (pinfunction "OSCI/CLKI/CN23/RC12_39") (pintype "bidirectional"))
      (node (ref "Y1") (pin "1") (pinfunction "OSC1_1") (pintype "passive"))
    )
    (net (code "133") (name "OSC1_2") (class "Default")
      (node (ref "C51") (pin "2") (pinfunction "2_2") (pintype "passive"))
      (node (ref "U8") (pin "13") (pinfunction "OSC1/CLKIN_13") (pintype "input"))
      (node (ref "Y2") (pin "2") (pinfunction "OSC2_2") (pintype "passive"))
    )
    (net (code "134") (name "OSC2") (class "Default")
      (node (ref "C2") (pin "2") (pinfunction "2_2") (pintype "passive"))
      (node (ref "U1") (pin "40") (pinfunction "OSCO/CLKO/CN22/RC15_40") (pintype "bidirectional"))
      (node (ref "Y1") (pin "3") (pinfunction "OSC3_3") (pintype "passive"))
    )
    (net (code "135") (name "OSC2_2") (class "Default")
      (node (ref "C49") (pin "2") (pinfunction "2_2") (pintype "passive"))
      (node (ref "U8") (pin "14") (pinfunction "OSC2/CLKOUT_14") (pintype "output"))
      (node (ref "Y2") (pin "1") (pinfunction "OSC1_1") (pintype "passive"))
    )
    (net (code "136") (name "OUT_RL1") (class "Default")
      (node (ref "U8") (pin "19") (pinfunction "RD0/PSP0_19") (pintype "bidirectional"))
    )
    (net (code "137") (name "OUT_RL2") (class "Default")
      (node (ref "R54") (pin "1") (pinfunction "1_1") (pintype "passive"))
      (node (ref "U8") (pin "20") (pinfunction "RD1/PSP1_20") (pintype "bidirectional"))
    )
    (net (code "138") (name "OUT_RL3") (class "Default")
      (node (ref "R60") (pin "1") (pinfunction "1_1") (pintype "passive"))
      (node (ref "U8") (pin "21") (pinfunction "RD2/PSP2_21") (pintype "bidirectional"))
    )
    (net (code "139") (name "OUT_RL4") (class "Default")
      (node (ref "R67") (pin "1") (pinfunction "1_1") (pintype "passive"))
      (node (ref "U8") (pin "22") (pinfunction "RD3/PSP3_22") (pintype "bidirectional"))
    )
    (net (code "140") (name "OUT_RL5") (class "Default")
      (node (ref "R79") (pin "1") (pinfunction "1_1") (pintype "passive"))
      (node (ref "U8") (pin "27") (pinfunction "RD4/PSP4_27") (pintype "bidirectional"))
    )
    (net (code "141") (name "OUT_RL6") (class "Default")
      (node (ref "R47") (pin "1") (pinfunction "1_1") (pintype "passive"))
      (node (ref "U8") (pin "28") (pinfunction "RD5/PSP5_28") (pintype "bidirectional"))
    )
    (net (code "142") (name "OUT_RL7") (class "Default")
      (node (ref "R56") (pin "1") (pinfunction "1_1") (pintype "passive"))
      (node (ref "U8") (pin "29") (pinfunction "RD6/PSP6_29") (pintype "bidirectional"))
    )
    (net (code "143") (name "OUT_RL8") (class "Default")
      (node (ref "R62") (pin "1") (pinfunction "1_1") (pintype "passive"))
      (node (ref "U8") (pin "30") (pinfunction "RD7/PSP7_30") (pintype "bidirectional"))
    )
    (net (code "144") (name "OUT_RL9") (class "Default")
      (node (ref "U8") (pin "8") (pinfunction "RE0/~{RD}/AN5_8") (pintype "bidirectional"))
    )
    (net (code "145") (name "OUT_RL10") (class "Default")
      (node (ref "U8") (pin "9") (pinfunction "RE1/~{WR}/AN6_9") (pintype "bidirectional"))
    )
    (net (code "146") (name "PGC2") (class "Default")
      (node (ref "J1") (pin "5") (pinfunction "5_5") (pintype "passive"))
      (node (ref "U1") (pin "17") (pinfunction "PGEC2/AN6/RP6/CN24/RB6_17") (pintype "bidirectional"))
    )
    (net (code "147") (name "PGC3") (class "Default")
      (node (ref "J6") (pin "5") (pinfunction "5_5") (pintype "passive"))
      (node (ref "R98") (pin "2") (pinfunction "2_2") (pintype "passive"))
      (node (ref "U6") (pin "12") (pinfunction "RA1/AN1/CIN-/VREF/ICSPCLK_12") (pintype "bidirectional"))
    )
    (net (code "148") (name "PGD") (class "Default")
      (node (ref "J4") (pin "5") (pinfunction "5_5") (pintype "passive"))
      (node (ref "J9") (pin "4") (pinfunction "4_4") (pintype "passive"))
      (node (ref "LCD1") (pin "4") (pinfunction "RS_4") (pintype "input"))
      (node (ref "U8") (pin "40") (pinfunction "RB7/PGD_40") (pintype "bidirectional"))
    )
    (net (code "149") (name "PGD2") (class "Default")
      (node (ref "J1") (pin "4") (pinfunction "4_4") (pintype "passive"))
      (node (ref "U1") (pin "18") (pinfunction "PGED2/RCV/RP7/AN7/CN25/RB7_18") (pintype "bidirectional"))
    )
    (net (code "150") (name "PGD3") (class "Default")
      (node (ref "J6") (pin "4") (pinfunction "4_4") (pintype "passive"))
      (node (ref "R50") (pin "2") (pinfunction "2_2") (pintype "passive"))
      (node (ref "U6") (pin "13") (pinfunction "RA0/AN0/CIN+/ICSPDAT_13") (pintype "bidirectional"))
    )
    (net (code "151") (name "PGND") (class "Default")
      (node (ref "C20") (pin "1") (pinfunction "1_1") (pintype "passive"))
      (node (ref "C21") (pin "1") (pinfunction "1_1") (pintype "passive"))
      (node (ref "C22") (pin "1") (pinfunction "1_1") (pintype "passive"))
      (node (ref "C23") (pin "2") (pinfunction "2_2") (pintype "passive"))
      (node (ref "C24") (pin "1") (pinfunction "1_1") (pintype "passive"))
      (node (ref "C25") (pin "1") (pinfunction "1_1") (pintype "passive"))
      (node (ref "C26") (pin "1") (pinfunction "1_1") (pintype "passive"))
      (node (ref "C29") (pin "2") (pinfunction "2_2") (pintype "passive"))
      (node (ref "C30") (pin "1") (pinfunction "1_1") (pintype "passive"))
      (node (ref "C31") (pin "1") (pinfunction "1_1") (pintype "passive"))
      (node (ref "C32") (pin "1") (pinfunction "1_1") (pintype "passive"))
      (node (ref "C33") (pin "2") (pinfunction "2_2") (pintype "passive"))
      (node (ref "C34") (pin "1") (pinfunction "1_1") (pintype "passive"))
      (node (ref "C35") (pin "1") (pinfunction "1_1") (pintype "passive"))
      (node (ref "C36") (pin "1") (pinfunction "1_1") (pintype "passive"))
      (node (ref "C50") (pin "1") (pinfunction "1_1") (pintype "passive"))
      (node (ref "D23") (pin "1") (pinfunction "A_1") (pintype "passive"))
      (node (ref "D24") (pin "1") (pinfunction "A_1") (pintype "passive"))
      (node (ref "D30") (pin "1") (pinfunction "A_1") (pintype "passive"))
      (node (ref "D32") (pin "1") (pinfunction "A_1") (pintype "passive"))
      (node (ref "D35") (pin "1") (pinfunction "A_1") (pintype "passive"))
      (node (ref "D36") (pin "1") (pinfunction "A_1") (pintype "passive"))
      (node (ref "D47") (pin "1") (pinfunction "A_1") (pintype "passive"))
      (node (ref "D48") (pin "1") (pinfunction "A_1") (pintype "passive"))
      (node (ref "J6") (pin "3") (pinfunction "3_3") (pintype "passive"))
      (node (ref "P7") (pin "2") (pinfunction "2_2") (pintype "passive"))
      (node (ref "R42") (pin "1") (pinfunction "1_1") (pintype "passive"))
      (node (ref "R43") (pin "1") (pinfunction "1_1") (pintype "passive"))
      (node (ref "R49") (pin "1") (pinfunction "1_1") (pintype "passive"))
      (node (ref "R57") (pin "2") (pinfunction "2_2") (pintype "passive"))
      (node (ref "R63") (pin "2") (pinfunction "2_2") (pintype "passive"))
      (node (ref "R76") (pin "1") (pinfunction "1_1") (pintype "passive"))
      (node (ref "R77") (pin "1") (pinfunction "1_1") (pintype "passive"))
      (node (ref "R87") (pin "1") (pinfunction "1_1") (pintype "passive"))
      (node (ref "R88") (pin "1") (pinfunction "1_1") (pintype "passive"))
      (node (ref "R95") (pin "1") (pinfunction "1_1") (pintype "passive"))
      (node (ref "R96") (pin "1") (pinfunction "1_1") (pintype "passive"))
      (node (ref "U10") (pin "2") (pinfunction "K_2") (pintype "passive"))
      (node (ref "U11") (pin "2") (pinfunction "GND_2") (pintype "power_in"))
      (node (ref "U12") (pin "2") (pinfunction "K_2") (pintype "passive"))
      (node (ref "U13") (pin "2") (pinfunction "GND_2") (pintype "power_in"))
      (node (ref "U14") (pin "2") (pinfunction "K_2") (pintype "passive"))
      (node (ref "U15") (pin "2") (pinfunction "K_2") (pintype "passive"))
      (node (ref "U16") (pin "2") (pinfunction "GND_2") (pintype "power_in"))
      (node (ref "U17") (pin "2") (pinfunction "K_2") (pintype "passive"))
      (node (ref "U18") (pin "2") (pinfunction "K_2") (pintype "passive"))
      (node (ref "U6") (pin "14") (pinfunction "VSS_14") (pintype "power_in"))
      (node (ref "U9") (pin "2") (pinfunction "K_2") (pintype "passive"))
    )
    (net (code "152") (name "PIC_D+") (class "Default")
      (node (ref "J3") (pin "3") (pinfunction "D+_3") (pintype "input"))
      (node (ref "U1") (pin "37") (pinfunction "D+/RG2_37") (pintype "bidirectional"))
      (node (ref "U4") (pin "3") (pinfunction "IO_3") (pintype "bidirectional"))
    )
    (net (code "153") (name "PIC_D-") (class "Default")
      (node (ref "J3") (pin "2") (pinfunction "D-_2") (pintype "input"))
      (node (ref "U1") (pin "36") (pinfunction "D-/RG3_36") (pintype "bidirectional"))
      (node (ref "U4") (pin "2") (pinfunction "IO_2") (pintype "bidirectional"))
    )
    (net (code "154") (name "RB0") (class "Default")
      (node (ref "J9") (pin "7") (pinfunction "7_7") (pintype "passive"))
      (node (ref "LCD1") (pin "7") (pinfunction "DB0_7") (pintype "bidirectional"))
    )
    (net (code "155") (name "RB1") (class "Default")
      (node (ref "J9") (pin "8") (pinfunction "8_8") (pintype "passive"))
      (node (ref "LCD1") (pin "8") (pinfunction "DB1_8") (pintype "bidirectional"))
    )
    (net (code "156") (name "RB2") (class "Default")
      (node (ref "J8") (pin "1") (pinfunction "1_1") (pintype "passive"))
      (node (ref "LCD1") (pin "9") (pinfunction "DB2_9") (pintype "input"))
    )
    (net (code "157") (name "RB3") (class "Default")
      (node (ref "J8") (pin "2") (pinfunction "2_2") (pintype "passive"))
      (node (ref "LCD1") (pin "10") (pinfunction "DB3_10") (pintype "bidirectional"))
    )
    (net (code "158") (name "RB4") (class "Default")
      (node (ref "J8") (pin "3") (pinfunction "3_3") (pintype "passive"))
      (node (ref "LCD1") (pin "11") (pinfunction "DB4_11") (pintype "bidirectional"))
      (node (ref "U8") (pin "33") (pinfunction "RB0/INT_33") (pintype "bidirectional"))
    )
    (net (code "159") (name "RB5") (class "Default")
      (node (ref "J8") (pin "4") (pinfunction "4_4") (pintype "passive"))
      (node (ref "LCD1") (pin "12") (pinfunction "DB5_12") (pintype "bidirectional"))
      (node (ref "U8") (pin "34") (pinfunction "RB1_34") (pintype "bidirectional"))
    )
    (net (code "160") (name "RB6") (class "Default")
      (node (ref "J8") (pin "5") (pinfunction "5_5") (pintype "passive"))
      (node (ref "LCD1") (pin "13") (pinfunction "DB6_13") (pintype "bidirectional"))
      (node (ref "U8") (pin "35") (pinfunction "RB2_35") (pintype "bidirectional"))
    )
    (net (code "161") (name "RB7") (class "Default")
      (node (ref "J8") (pin "6") (pinfunction "6_6") (pintype "passive"))
      (node (ref "LCD1") (pin "14") (pinfunction "DB7_14") (pintype "bidirectional"))
      (node (ref "U8") (pin "36") (pinfunction "RB3/PGM_36") (pintype "bidirectional"))
    )
    (net (code "162") (name "RTS") (class "Default")
      (node (ref "R4") (pin "2") (pinfunction "2_2") (pintype "passive"))
      (node (ref "U1") (pin "51") (pinfunction "RP22/PMBE/CN52/RD3_51") (pintype "bidirectional"))
    )
    (net (code "163") (name "RW") (class "Default")
      (node (ref "J9") (pin "5") (pinfunction "5_5") (pintype "passive"))
      (node (ref "LCD1") (pin "5") (pinfunction "R/~{W}_5") (pintype "bidirectional"))
    )
    (net (code "164") (name "RXD") (class "Default")
      (node (ref "J7") (pin "4") (pinfunction "4_4") (pintype "passive"))
      (node (ref "R5") (pin "2") (pinfunction "2_2") (pintype "passive"))
      (node (ref "R99") (pin "2") (pinfunction "2_2") (pintype "passive"))
      (node (ref "U1") (pin "49") (pinfunction "RP24/VCPCON/CN50/RD1_49") (pintype "bidirectional"))
    )
    (net (code "165") (name "SCK") (class "Default")
      (node (ref "RV2") (pin "2") (pinfunction "2_2") (pintype "passive"))
      (node (ref "TFLASH1") (pin "P5") (pinfunction "SCLK_P5") (pintype "passive"))
      (node (ref "U1") (pin "4") (pinfunction "PMA5/RP21/C1IND/CN8/RG6_4") (pintype "bidirectional"))
      (node (ref "U2") (pin "6") (pinfunction "SCK_6") (pintype "input"))
    )
    (net (code "166") (name "SDI") (class "Default")
      (node (ref "R10") (pin "2") (pinfunction "2_2") (pintype "passive"))
      (node (ref "RV1") (pin "2") (pinfunction "2_2") (pintype "passive"))
      (node (ref "TFLASH1") (pin "P7") (pinfunction "DO_P7") (pintype "passive"))
      (node (ref "U1") (pin "5") (pinfunction "RP26/PMA4/C1INC/CN9/RG7_5") (pintype "bidirectional"))
      (node (ref "U2") (pin "2") (pinfunction "SO_2") (pintype "output"))
    )
    (net (code "167") (name "SDO") (class "Default")
      (node (ref "RV3") (pin "2") (pinfunction "2_2") (pintype "passive"))
      (node (ref "TFLASH1") (pin "P3") (pinfunction "DI_P3") (pintype "passive"))
      (node (ref "U1") (pin "6") (pinfunction "PMA3/RP19/C2IND/CN10/RG8_6") (pintype "bidirectional"))
      (node (ref "U2") (pin "5") (pinfunction "SI_5") (pintype "input"))
    )
    (net (code "168") (name "SPIFLASH_CS") (class "Default")
      (node (ref "R9") (pin "1") (pinfunction "1_1") (pintype "passive"))
      (node (ref "U1") (pin "1") (pinfunction "PMD5/CN63/RE5_1") (pintype "bidirectional"))
      (node (ref "U2") (pin "1") (pinfunction "CS_1") (pintype "input"))
    )
    (net (code "169") (name "SPIFLASH_WP") (class "Default")
      (node (ref "R14") (pin "2") (pinfunction "2_2") (pintype "passive"))
      (node (ref "U1") (pin "64") (pinfunction "PMD4/CN62/RE4_64") (pintype "bidirectional"))
      (node (ref "U2") (pin "3") (pinfunction "WP_3") (pintype "power_in"))
    )
    (net (code "170") (name "T1") (class "Default")
      (node (ref "D29") (pin "1") (pinfunction "A_1") (pintype "passive"))
      (node (ref "D30") (pin "2") (pinfunction "K_2") (pintype "passive"))
      (node (ref "P18") (pin "1") (pinfunction "1_1") (pintype "passive"))
      (node (ref "T1") (pin "3") (pinfunction "Sec1+_3") (pintype "passive"))
    )
    (net (code "171") (name "T2") (class "Default")
      (node (ref "D31") (pin "1") (pinfunction "A_1") (pintype "passive"))
      (node (ref "D32") (pin "2") (pinfunction "K_2") (pintype "passive"))
      (node (ref "P18") (pin "2") (pinfunction "2_2") (pintype "passive"))
      (node (ref "T1") (pin "4") (pinfunction "Sec1-_4") (pintype "passive"))
    )
    (net (code "172") (name "T3") (class "Default")
      (node (ref "D37") (pin "1") (pinfunction "A_1") (pintype "passive"))
      (node (ref "D38") (pin "2") (pinfunction "K_2") (pintype "passive"))
      (node (ref "P20") (pin "1") (pinfunction "1_1") (pintype "passive"))
      (node (ref "T1") (pin "5") (pinfunction "Sec2+_5") (pintype "passive"))
    )
    (net (code "173") (name "T4") (class "Default")
      (node (ref "D39") (pin "1") (pinfunction "A_1") (pintype "passive"))
      (node (ref "D40") (pin "2") (pinfunction "K_2") (pintype "passive"))
      (node (ref "P20") (pin "2") (pinfunction "2_2") (pintype "passive"))
      (node (ref "T1") (pin "6") (pinfunction "Sec2-_6") (pintype "passive"))
    )
    (net (code "174") (name "TA") (class "Default")
      (node (ref "P17") (pin "2") (pinfunction "2_2") (pintype "passive"))
      (node (ref "P19") (pin "1") (pinfunction "1_1") (pintype "passive"))
      (node (ref "T1") (pin "1") (pinfunction "Pri+_1") (pintype "passive"))
    )
    (net (code "175") (name "TB") (class "Default")
      (node (ref "P17") (pin "1") (pinfunction "1_1") (pintype "passive"))
      (node (ref "P19") (pin "2") (pinfunction "2_2") (pintype "passive"))
      (node (ref "T1") (pin "2") (pinfunction "Pri-_2") (pintype "passive"))
    )
    (net (code "176") (name "TF_CS") (class "Default")
      (node (ref "R13") (pin "1") (pinfunction "1_1") (pintype "passive"))
      (node (ref "RV4") (pin "2") (pinfunction "2_2") (pintype "passive"))
      (node (ref "TFLASH1") (pin "P2") (pinfunction "CS_P2") (pintype "passive"))
      (node (ref "U1") (pin "32") (pinfunction "PMA8/RP17/SCL2/CN18/RF5_32") (pintype "bidirectional"))
    )
    (net (code "177") (name "TXD") (class "Default")
      (node (ref "J7") (pin "5") (pinfunction "5_5") (pintype "passive"))
      (node (ref "R36") (pin "1") (pinfunction "1_1") (pintype "passive"))
      (node (ref "R6") (pin "2") (pinfunction "2_2") (pintype "passive"))
      (node (ref "U1") (pin "50") (pinfunction "DPH/RP23/CN51/RD2_50") (pintype "bidirectional"))
    )
    (net (code "178") (name "USB_ID") (class "Default")
      (node (ref "J3") (pin "4") (pinfunction "GND_4") (pintype "power_in"))
      (node (ref "U1") (pin "33") (pinfunction "RP16/USBID/CN71/RF3_33") (pintype "bidirectional"))
    )
    (net (code "179") (name "VCC") (class "Default")
      (node (ref "D1") (pin "1") (pinfunction "A_1") (pintype "passive"))
      (node (ref "D1") (pin "2") (pinfunction "A_2") (pintype "passive"))
      (node (ref "J2") (pin "3") (pinfunction "3_3") (pintype "passive"))
      (node (ref "J7") (pin "2") (pinfunction "2_2") (pintype "passive"))
      (node (ref "U21") (pin "4") (pinfunction "C_4") (pintype "passive"))
    )
    (net (code "180") (name "VCC_ISOL") (class "Default")
      (node (ref "C23") (pin "1") (pinfunction "1_1") (pintype "passive"))
      (node (ref "C26") (pin "2") (pinfunction "2_2") (pintype "passive"))
      (node (ref "C29") (pin "1") (pinfunction "1_1") (pintype "passive"))
      (node (ref "C32") (pin "2") (pinfunction "2_2") (pintype "passive"))
      (node (ref "C33") (pin "1") (pinfunction "1_1") (pintype "passive"))
      (node (ref "C36") (pin "2") (pinfunction "2_2") (pintype "passive"))
      (node (ref "D29") (pin "2") (pinfunction "K_2") (pintype "passive"))
      (node (ref "D31") (pin "2") (pinfunction "K_2") (pintype "passive"))
      (node (ref "U11") (pin "1") (pinfunction "IN_1") (pintype "power_in"))
      (node (ref "U13") (pin "1") (pinfunction "IN_1") (pintype "power_in"))
      (node (ref "U16") (pin "1") (pinfunction "IN_1") (pintype "power_in"))
    )
    (net (code "181") (name "VD") (class "Default")
      (node (ref "J9") (pin "3") (pinfunction "3_3") (pintype "passive"))
      (node (ref "LCD1") (pin "3") (pinfunction "VD_3") (pintype "output"))
      (node (ref "R52") (pin "3") (pinfunction "TAP_3") (pintype "passive"))
    )
    (net (code "182") (name "VDDCORE") (class "Default")
      (node (ref "C3") (pin "2") (pinfunction "2_2") (pintype "passive"))
      (node (ref "C4") (pin "2") (pinfunction "2_2") (pintype "passive"))
      (node (ref "U1") (pin "56") (pinfunction "VCAP/VDDCORE_56") (pintype "power_in"))
    )
    (net (code "183") (name "WIFI_CS") (class "Default")
      (node (ref "U1") (pin "22") (pinfunction "PMA7/RP9/AN9/CN27/RB9_22") (pintype "bidirectional"))
      (node (ref "U3") (pin "23") (pinfunction "CS_23") (pintype "input"))
    )
    (net (code "184") (name "WIFI_EN") (class "Default")
      (node (ref "R25") (pin "2") (pinfunction "2_2") (pintype "passive"))
      (node (ref "U1") (pin "23") (pinfunction "TMS/PMA13/AN10/CVREF/CN28/RB10_23") (pintype "bidirectional"))
      (node (ref "U3") (pin "20") (pinfunction "HIBERNATE_20") (pintype "input"))
    )
    (net (code "185") (name "WIFI_INT") (class "Default")
      (node (ref "R18") (pin "1") (pinfunction "1_1") (pintype "passive"))
      (node (ref "U1") (pin "21") (pinfunction "RP8/AN8/CN26/RB8_21") (pintype "bidirectional"))
      (node (ref "U3") (pin "33") (pinfunction "INT_33") (pintype "output"))
    )
    (net (code "186") (name "WIFI_RESET") (class "Default")
      (node (ref "C15") (pin "2") (pinfunction "2_2") (pintype "passive"))
      (node (ref "R16") (pin "1") (pinfunction "1_1") (pintype "passive"))
      (node (ref "U1") (pin "31") (pinfunction "PMA9/RP10/SDA2/CN17/RF4_31") (pintype "bidirectional"))
      (node (ref "U3") (pin "7") (pinfunction "RESET_7") (pintype "input"))
    )
    (net (code "187") (name "WIFI_SCK") (class "Default")
      (node (ref "U1") (pin "14") (pinfunction "VMIO/RP13/C2INB/AN2/CN4/RB2_14") (pintype "bidirectional"))
      (node (ref "U3") (pin "34") (pinfunction "SCK_34") (pintype "input"))
    )
    (net (code "188") (name "WIFI_SDI") (class "Default")
      (node (ref "U1") (pin "15") (pinfunction "PGEC1/RP1/VREF-/AN1/CN3/RB1_15") (pintype "bidirectional"))
      (node (ref "U3") (pin "32") (pinfunction "SDO_32") (pintype "input"))
    )
    (net (code "189") (name "WIFI_SDO") (class "Default")
      (node (ref "U1") (pin "16") (pinfunction "PGED1/RP0/PMA6/VREF+/AN0/CN2/RB0_16") (pintype "bidirectional"))
      (node (ref "U3") (pin "35") (pinfunction "SDI_35") (pintype "input"))
    )
    (net (code "190") (name "unconnected-(J1-Pad6)") (class "Default")
      (node (ref "J1") (pin "6") (pinfunction "6_6") (pintype "passive+no_connect"))
    )
    (net (code "191") (name "unconnected-(J4-Pad6)") (class "Default")
      (node (ref "J4") (pin "6") (pinfunction "6_6") (pintype "passive+no_connect"))
    )
    (net (code "192") (name "unconnected-(J5-D+-Pad3)") (class "Default")
      (node (ref "J5") (pin "3") (pinfunction "D+_3") (pintype "input+no_connect"))
    )
    (net (code "193") (name "unconnected-(J5-D--Pad2)") (class "Default")
      (node (ref "J5") (pin "2") (pinfunction "D-_2") (pintype "input+no_connect"))
    )
    (net (code "194") (name "unconnected-(J6-Pad6)") (class "Default")
      (node (ref "J6") (pin "6") (pinfunction "6_6") (pintype "passive+no_connect"))
    )
    (net (code "195") (name "unconnected-(J7-Pad3)") (class "Default")
      (node (ref "J7") (pin "3") (pinfunction "3_3") (pintype "passive"))
    )
    (net (code "196") (name "unconnected-(J7-Pad6)") (class "Default")
      (node (ref "J7") (pin "6") (pinfunction "6_6") (pintype "passive"))
    )
    (net (code "197") (name "unconnected-(U1-C3INA{slash}CN16{slash}RD7-Pad55)") (class "Default")
      (node (ref "U1") (pin "55") (pinfunction "C3INA/CN16/RD7_55") (pintype "bidirectional+no_connect"))
    )
    (net (code "198") (name "unconnected-(U1-C3INB{slash}CN15{slash}RD6-Pad54)") (class "Default")
      (node (ref "U1") (pin "54") (pinfunction "C3INB/CN15/RD6_54") (pintype "bidirectional+no_connect"))
    )
    (net (code "199") (name "unconnected-(U1-CTPLS{slash}RP14{slash}PMA1{slash}AN14{slash}CN32{slash}RB14-Pad29)") (class "Default")
      (node (ref "U1") (pin "29") (pinfunction "CTPLS/RP14/PMA1/AN14/CN32/RB14_29") (pintype "bidirectional+no_connect"))
    )
    (net (code "200") (name "unconnected-(U1-PGEC3{slash}RP18{slash}VBUSON{slash}C1INA{slash}AN5{slash}CN7{slash}RB5-Pad11)") (class "Default")
      (node (ref "U1") (pin "11") (pinfunction "PGEC3/RP18/VBUSON/C1INA/AN5/CN7/RB5_11") (pintype "bidirectional+no_connect"))
    )
    (net (code "201") (name "unconnected-(U1-PGED3{slash}RP28{slash}USBOEN{slash}C1INB{slash}AN4{slash}CN6{slash}RB4-Pad12)") (class "Default")
      (node (ref "U1") (pin "12") (pinfunction "PGED3/RP28/USBOEN/C1INB/AN4/CN6/RB4_12") (pintype "bidirectional+no_connect"))
    )
    (net (code "202") (name "unconnected-(U1-PMD0{slash}CN58{slash}RE0-Pad60)") (class "Default")
      (node (ref "U1") (pin "60") (pinfunction "PMD0/CN58/RE0_60") (pintype "bidirectional+no_connect"))
    )
    (net (code "203") (name "unconnected-(U1-PMD1{slash}CN59{slash}RE1-Pad61)") (class "Default")
      (node (ref "U1") (pin "61") (pinfunction "PMD1/CN59/RE1_61") (pintype "bidirectional+no_connect"))
    )
    (net (code "204") (name "unconnected-(U1-PMD2{slash}CN60{slash}RE2-Pad62)") (class "Default")
      (node (ref "U1") (pin "62") (pinfunction "PMD2/CN60/RE2_62") (pintype "bidirectional+no_connect"))
    )
    (net (code "205") (name "unconnected-(U1-PMD3{slash}CN61{slash}RE3-Pad63)") (class "Default")
      (node (ref "U1") (pin "63") (pinfunction "PMD3/CN61/RE3_63") (pintype "bidirectional+no_connect"))
    )
    (net (code "206") (name "unconnected-(U1-PMD6{slash}SCL3{slash}CN64{slash}RE6-Pad2)") (class "Default")
      (node (ref "U1") (pin "2") (pinfunction "PMD6/SCL3/CN64/RE6_2") (pintype "bidirectional+no_connect"))
    )
    (net (code "207") (name "unconnected-(U1-PMD7{slash}SDA3{slash}CN65{slash}RE7-Pad3)") (class "Default")
      (node (ref "U1") (pin "3") (pinfunction "PMD7/SDA3/CN65/RE7_3") (pintype "bidirectional+no_connect"))
    )
    (net (code "208") (name "unconnected-(U1-PMRD{slash}RP20{slash}CN14{slash}RD5-Pad53)") (class "Default")
      (node (ref "U1") (pin "53") (pinfunction "PMRD/RP20/CN14/RD5_53") (pintype "bidirectional+no_connect"))
    )
    (net (code "209") (name "unconnected-(U1-PMWR{slash}RP25{slash}CN13{slash}RD4-Pad52)") (class "Default")
      (node (ref "U1") (pin "52") (pinfunction "PMWR/RP25/CN13/RD4_52") (pintype "bidirectional+no_connect"))
    )
    (net (code "210") (name "unconnected-(U1-RP2{slash}DMLN{slash}RTCC{slash}CN53{slash}RD8-Pad42)") (class "Default")
      (node (ref "U1") (pin "42") (pinfunction "RP2/DMLN/RTCC/CN53/RD8_42") (pintype "bidirectional+no_connect"))
    )
    (net (code "211") (name "unconnected-(U1-RP27{slash}PMA2{slash}C2INC{slash}CN11{slash}RG9-Pad8)") (class "Default")
      (node (ref "U1") (pin "8") (pinfunction "RP27/PMA2/C2INC/CN11/RG9_8") (pintype "bidirectional+no_connect"))
    )
    (net (code "212") (name "unconnected-(U1-RP29{slash}PMA0{slash}AN15{slash}REFO{slash}CN12{slash}RB15-Pad30)") (class "Default")
      (node (ref "U1") (pin "30") (pinfunction "RP29/PMA0/AN15/REFO/CN12/RB15_30") (pintype "bidirectional+no_connect"))
    )
    (net (code "213") (name "unconnected-(U1-TCK{slash}PMA11{slash}AN12{slash}CTED2{slash}CN30{slash}RB12-Pad27)") (class "Default")
      (node (ref "U1") (pin "27") (pinfunction "TCK/PMA11/AN12/CTED2/CN30/RB12_27") (pintype "bidirectional+no_connect"))
    )
    (net (code "214") (name "unconnected-(U1-TDI{slash}PMA10{slash}AN13{slash}CTED1{slash}CN31{slash}RB13-Pad28)") (class "Default")
      (node (ref "U1") (pin "28") (pinfunction "TDI/PMA10/AN13/CTED1/CN31/RB13_28") (pintype "bidirectional+no_connect"))
    )
    (net (code "215") (name "unconnected-(U1-TDO{slash}AN11{slash}PMA12{slash}CN29{slash}RB11-Pad24)") (class "Default")
      (node (ref "U1") (pin "24") (pinfunction "TDO/AN11/PMA12/CN29/RB11_24") (pintype "bidirectional+no_connect"))
    )
    (net (code "216") (name "unconnected-(U1-VBUSST{slash}VCMPST1{slash}CN68{slash}RF0-Pad58)") (class "Default")
      (node (ref "U1") (pin "58") (pinfunction "VBUSST/VCMPST1/CN68/RF0_58") (pintype "bidirectional+no_connect"))
    )
    (net (code "217") (name "unconnected-(U1-VCMPST2{slash}CN69{slash}RF1-Pad59)") (class "Default")
      (node (ref "U1") (pin "59") (pinfunction "VCMPST2/CN69/RF1_59") (pintype "bidirectional+no_connect"))
    )
    (net (code "218") (name "unconnected-(U3-JTAG_TDI-Pad6)") (class "Default")
      (node (ref "U3") (pin "6") (pinfunction "JTAG_TDI_6") (pintype "input+no_connect"))
    )
    (net (code "219") (name "unconnected-(U3-JTAG_TDO-Pad3)") (class "Default")
      (node (ref "U3") (pin "3") (pinfunction "JTAG_TDO_3") (pintype "output+no_connect"))
    )
    (net (code "220") (name "unconnected-(U3-JTAG_TMS-Pad5)") (class "Default")
      (node (ref "U3") (pin "5") (pinfunction "JTAG_TMS_5") (pintype "input+no_connect"))
    )
    (net (code "221") (name "unconnected-(U3-NC-Pad2)") (class "Default")
      (node (ref "U3") (pin "2") (pinfunction "NC_2") (pintype "power_in+no_connect"))
    )
    (net (code "222") (name "unconnected-(U3-NC-Pad8)") (class "Default")
      (node (ref "U3") (pin "8") (pinfunction "NC_8") (pintype "power_in+no_connect"))
    )
    (net (code "223") (name "unconnected-(U3-NC-Pad11)") (class "Default")
      (node (ref "U3") (pin "11") (pinfunction "NC_11") (pintype "power_in+no_connect"))
    )
    (net (code "224") (name "unconnected-(U3-NC-Pad12)") (class "Default")
      (node (ref "U3") (pin "12") (pinfunction "NC_12") (pintype "power_in+no_connect"))
    )
    (net (code "225") (name "unconnected-(U3-NC-Pad13)") (class "Default")
      (node (ref "U3") (pin "13") (pinfunction "NC_13") (pintype "power_in+no_connect"))
    )
    (net (code "226") (name "unconnected-(U3-NC-Pad14)") (class "Default")
      (node (ref "U3") (pin "14") (pinfunction "NC_14") (pintype "power_in+no_connect"))
    )
    (net (code "227") (name "unconnected-(U3-NC-Pad15)") (class "Default")
      (node (ref "U3") (pin "15") (pinfunction "NC_15") (pintype "power_in+no_connect"))
    )
    (net (code "228") (name "unconnected-(U3-NC-Pad22)") (class "Default")
      (node (ref "U3") (pin "22") (pinfunction "NC_22") (pintype "power_in+no_connect"))
    )
    (net (code "229") (name "unconnected-(U3-NC-Pad24)") (class "Default")
      (node (ref "U3") (pin "24") (pinfunction "NC_24") (pintype "power_in+no_connect"))
    )
    (net (code "230") (name "unconnected-(U3-NC-Pad31)") (class "Default")
      (node (ref "U3") (pin "31") (pinfunction "NC_31") (pintype "power_in+no_connect"))
    )
    (net (code "231") (name "unconnected-(U3-UART_RX-Pad26)") (class "Default")
      (node (ref "U3") (pin "26") (pinfunction "UART_RX_26") (pintype "input+no_connect"))
    )
    (net (code "232") (name "unconnected-(U3-UART_TX-Pad27)") (class "Default")
      (node (ref "U3") (pin "27") (pinfunction "UART_TX_27") (pintype "output+no_connect"))
    )
    (net (code "233") (name "unconnected-(U6-RA4{slash}~{T1G}{slash}OSC2{slash}AN3{slash}CLKOUT-Pad3)") (class "Default")
      (node (ref "U6") (pin "3") (pinfunction "RA4/~{T1G}/OSC2/AN3/CLKOUT_3") (pintype "bidirectional+no_connect"))
    )
    (net (code "234") (name "unconnected-(U6-RA5{slash}T1CKI{slash}OSC1{slash}CLKIN-Pad2)") (class "Default")
      (node (ref "U6") (pin "2") (pinfunction "RA5/T1CKI/OSC1/CLKIN_2") (pintype "bidirectional+no_connect"))
    )
    (net (code "235") (name "unconnected-(U6-RC3{slash}AN7-Pad7)") (class "Default")
      (node (ref "U6") (pin "7") (pinfunction "RC3/AN7_7") (pintype "bidirectional+no_connect"))
    )
    (net (code "236") (name "unconnected-(U6-RC4-Pad6)") (class "Default")
      (node (ref "U6") (pin "6") (pinfunction "RC4_6") (pintype "bidirectional+no_connect"))
    )
    (net (code "237") (name "unconnected-(U6-RC5-Pad5)") (class "Default")
      (node (ref "U6") (pin "5") (pinfunction "RC5_5") (pintype "bidirectional+no_connect"))
    )
    (net (code "238") (name "unconnected-(U8-RC2{slash}CCP1-Pad17)") (class "Default")
      (node (ref "U8") (pin "17") (pinfunction "RC2/CCP1_17") (pintype "bidirectional+no_connect"))
    )
    (net (code "239") (name "unconnected-(U8-RC3{slash}SCK{slash}SCL-Pad18)") (class "Default")
      (node (ref "U8") (pin "18") (pinfunction "RC3/SCK/SCL_18") (pintype "bidirectional+no_connect"))
    )
    (net (code "240") (name "unconnected-(U8-RC4{slash}SDI{slash}SDA-Pad23)") (class "Default")
      (node (ref "U8") (pin "23") (pinfunction "RC4/SDI/SDA_23") (pintype "bidirectional+no_connect"))
    )
    (net (code "241") (name "unconnected-(U8-RC5{slash}SDO-Pad24)") (class "Default")
      (node (ref "U8") (pin "24") (pinfunction "RC5/SDO_24") (pintype "bidirectional+no_connect"))
    )
    (net (code "242") (name "unconnected-(U8-RE2{slash}~{CS}{slash}AN7-Pad10)") (class "Default")
      (node (ref "U8") (pin "10") (pinfunction "RE2/~{CS}/AN7_10") (pintype "bidirectional+no_connect"))
    )
  )
)
